# buf_full_bts_v21.net
KiCad netlist of a schematic drawn in EAGLE
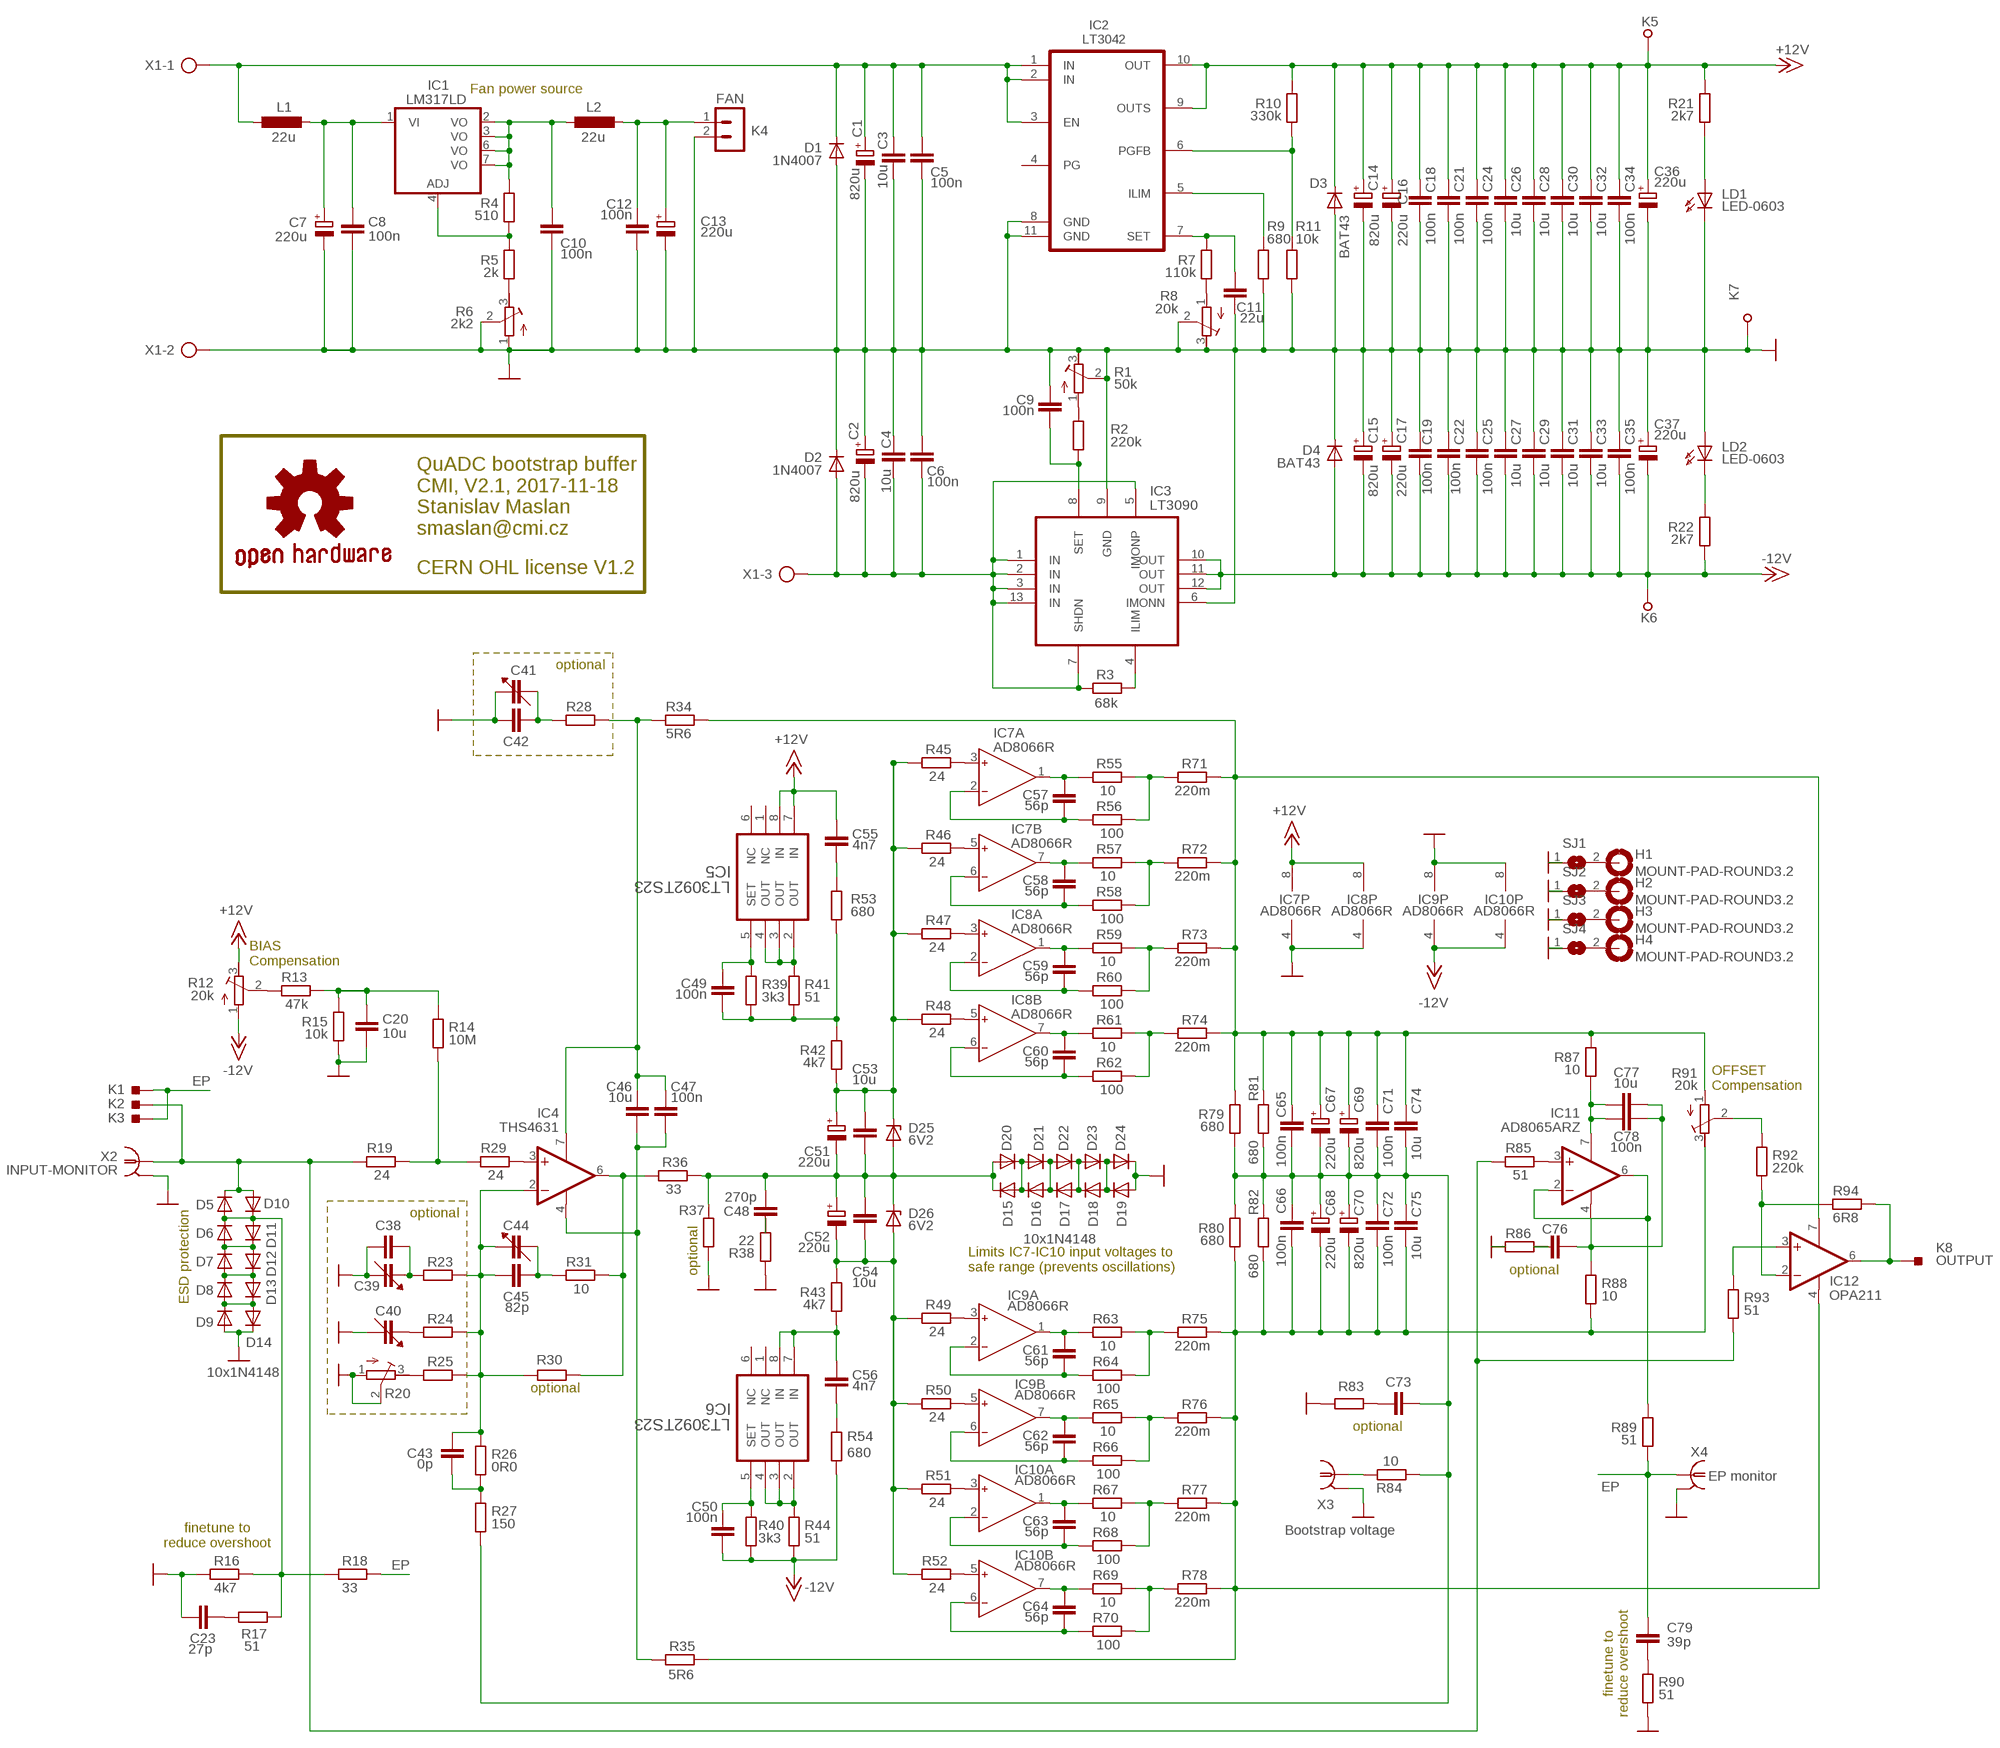
[diagram p0: schematic, sheet 1]

(export (version "E")
  (design (tool "Eeschema 10.0.6"))
  (components
    (comp (ref "C1")
      (value "820u")
      (footprint "eagle-import:E5-10,5")
      (libsource (lib "eagle-import") (part "CPOL-EUE5-10.5"))
    )
    (comp (ref "C2")
      (value "820u")
      (footprint "eagle-import:E5-10,5")
      (libsource (lib "eagle-import") (part "CPOL-EUE5-10.5"))
    )
    (comp (ref "C3")
      (value "10u")
      (footprint "eagle-import:C1210K")
      (libsource (lib "eagle-import") (part "C-EUC1210K"))
    )
    (comp (ref "C4")
      (value "10u")
      (footprint "eagle-import:C1210K")
      (libsource (lib "eagle-import") (part "C-EUC1210K"))
    )
    (comp (ref "C5")
      (value "100n")
      (footprint "eagle-import:X0805")
      (libsource (lib "eagle-import") (part "C-EUX0805"))
    )
    (comp (ref "C6")
      (value "100n")
      (footprint "eagle-import:X0805")
      (libsource (lib "eagle-import") (part "C-EUX0805"))
    )
    (comp (ref "C7")
      (value "220u")
      (footprint "eagle-import:E2,5-7")
      (libsource (lib "eagle-import") (part "CPOL-EUE2.5-7"))
    )
    (comp (ref "C8")
      (value "100n")
      (footprint "eagle-import:X0805")
      (libsource (lib "eagle-import") (part "C-EUX0805"))
    )
    (comp (ref "C9")
      (value "100n")
      (footprint "eagle-import:X0805")
      (libsource (lib "eagle-import") (part "C-EUX0805"))
    )
    (comp (ref "C10")
      (value "100n")
      (footprint "eagle-import:X0805")
      (libsource (lib "eagle-import") (part "C-EUX0805"))
    )
    (comp (ref "C11")
      (value "22u")
      (footprint "eagle-import:C1210K")
      (libsource (lib "eagle-import") (part "C-EUC1210K"))
    )
    (comp (ref "C12")
      (value "100n")
      (footprint "eagle-import:X0805")
      (libsource (lib "eagle-import") (part "C-EUX0805"))
    )
    (comp (ref "C13")
      (value "220u")
      (footprint "eagle-import:E2,5-7")
      (libsource (lib "eagle-import") (part "CPOL-EUE2.5-7"))
    )
    (comp (ref "C14")
      (value "820u")
      (footprint "eagle-import:E5-10,5")
      (libsource (lib "eagle-import") (part "CPOL-EUE5-10.5"))
    )
    (comp (ref "C15")
      (value "820u")
      (footprint "eagle-import:E5-10,5")
      (libsource (lib "eagle-import") (part "CPOL-EUE5-10.5"))
    )
    (comp (ref "C16")
      (value "220u")
      (footprint "eagle-import:E2,5-7")
      (libsource (lib "eagle-import") (part "CPOL-EUE2.5-7"))
    )
    (comp (ref "C17")
      (value "220u")
      (footprint "eagle-import:E2,5-7")
      (libsource (lib "eagle-import") (part "CPOL-EUE2.5-7"))
    )
    (comp (ref "C18")
      (value "100n")
      (footprint "eagle-import:X0805")
      (libsource (lib "eagle-import") (part "C-EUX0805"))
    )
    (comp (ref "C19")
      (value "100n")
      (footprint "eagle-import:X0805")
      (libsource (lib "eagle-import") (part "C-EUX0805"))
    )
    (comp (ref "C20")
      (value "10u")
      (footprint "eagle-import:C1210K")
      (libsource (lib "eagle-import") (part "C-EUC1210K"))
    )
    (comp (ref "C21")
      (value "100n")
      (footprint "eagle-import:X0805")
      (libsource (lib "eagle-import") (part "C-EUX0805"))
    )
    (comp (ref "C22")
      (value "100n")
      (footprint "eagle-import:X0805")
      (libsource (lib "eagle-import") (part "C-EUX0805"))
    )
    (comp (ref "C23")
      (value "27p")
      (footprint "eagle-import:C025-024X044")
      (libsource (lib "eagle-import") (part "C-EU025-024X044"))
    )
    (comp (ref "C24")
      (value "100n")
      (footprint "eagle-import:X0805")
      (libsource (lib "eagle-import") (part "C-EUX0805"))
    )
    (comp (ref "C25")
      (value "100n")
      (footprint "eagle-import:X0805")
      (libsource (lib "eagle-import") (part "C-EUX0805"))
    )
    (comp (ref "C26")
      (value "10u")
      (footprint "eagle-import:C1210K")
      (libsource (lib "eagle-import") (part "C-EUC1210K"))
    )
    (comp (ref "C27")
      (value "10u")
      (footprint "eagle-import:C1210K")
      (libsource (lib "eagle-import") (part "C-EUC1210K"))
    )
    (comp (ref "C28")
      (value "10u")
      (footprint "eagle-import:C1210K")
      (libsource (lib "eagle-import") (part "C-EUC1210K"))
    )
    (comp (ref "C29")
      (value "10u")
      (footprint "eagle-import:C1210K")
      (libsource (lib "eagle-import") (part "C-EUC1210K"))
    )
    (comp (ref "C30")
      (value "10u")
      (footprint "eagle-import:C1210K")
      (libsource (lib "eagle-import") (part "C-EUC1210K"))
    )
    (comp (ref "C31")
      (value "10u")
      (footprint "eagle-import:C1210K")
      (libsource (lib "eagle-import") (part "C-EUC1210K"))
    )
    (comp (ref "C32")
      (value "10u")
      (footprint "eagle-import:C1210K")
      (libsource (lib "eagle-import") (part "C-EUC1210K"))
    )
    (comp (ref "C33")
      (value "10u")
      (footprint "eagle-import:C1210K")
      (libsource (lib "eagle-import") (part "C-EUC1210K"))
    )
    (comp (ref "C34")
      (value "100n")
      (footprint "eagle-import:X0805")
      (libsource (lib "eagle-import") (part "C-EUX0805"))
    )
    (comp (ref "C35")
      (value "100n")
      (footprint "eagle-import:X0805")
      (libsource (lib "eagle-import") (part "C-EUX0805"))
    )
    (comp (ref "C36")
      (value "220u")
      (footprint "eagle-import:E2,5-7")
      (libsource (lib "eagle-import") (part "CPOL-EUE2.5-7"))
    )
    (comp (ref "C37")
      (value "220u")
      (footprint "eagle-import:E2,5-7")
      (libsource (lib "eagle-import") (part "CPOL-EUE2.5-7"))
    )
    (comp (ref "C38")
      (value "C-EU025-024X044")
      (footprint "eagle-import:C025-024X044")
      (libsource (lib "eagle-import") (part "C-EU025-024X044"))
    )
    (comp (ref "C39")
      (value "C_TRIMMER-9344")
      (footprint "eagle-import:CTRIMMER9344")
      (libsource (lib "eagle-import") (part "C_TRIMMER-9344"))
    )
    (comp (ref "C40")
      (value "C_TRIMMER-9344")
      (footprint "eagle-import:CTRIMMER9344")
      (libsource (lib "eagle-import") (part "C_TRIMMER-9344"))
    )
    (comp (ref "C41")
      (value "C_TRIMMER-9344")
      (footprint "eagle-import:CTRIMMER9344")
      (libsource (lib "eagle-import") (part "C_TRIMMER-9344"))
    )
    (comp (ref "C42")
      (value "C-EU025-024X044")
      (footprint "eagle-import:C025-024X044")
      (libsource (lib "eagle-import") (part "C-EU025-024X044"))
    )
    (comp (ref "C43")
      (value "0p")
      (footprint "eagle-import:C025-024X044")
      (libsource (lib "eagle-import") (part "C-EU025-024X044"))
    )
    (comp (ref "C44")
      (value "C_TRIMMER-9344")
      (footprint "eagle-import:CTRIMMER9344")
      (libsource (lib "eagle-import") (part "C_TRIMMER-9344"))
    )
    (comp (ref "C45")
      (value "82p")
      (footprint "eagle-import:C025-024X044")
      (libsource (lib "eagle-import") (part "C-EU025-024X044"))
    )
    (comp (ref "C46")
      (value "10u")
      (footprint "eagle-import:C1210K")
      (libsource (lib "eagle-import") (part "C-EUC1210K"))
    )
    (comp (ref "C47")
      (value "100n")
      (footprint "eagle-import:X0805")
      (libsource (lib "eagle-import") (part "C-EUX0805"))
    )
    (comp (ref "C48")
      (value "270p")
      (footprint "eagle-import:X0805")
      (libsource (lib "eagle-import") (part "C-EUX0805"))
    )
    (comp (ref "C49")
      (value "100n")
      (footprint "eagle-import:X0805")
      (libsource (lib "eagle-import") (part "C-EUX0805"))
    )
    (comp (ref "C50")
      (value "100n")
      (footprint "eagle-import:X0805")
      (libsource (lib "eagle-import") (part "C-EUX0805"))
    )
    (comp (ref "C51")
      (value "220u")
      (footprint "eagle-import:E2,5-7")
      (libsource (lib "eagle-import") (part "CPOL-EUE2.5-7"))
    )
    (comp (ref "C52")
      (value "220u")
      (footprint "eagle-import:E2,5-7")
      (libsource (lib "eagle-import") (part "CPOL-EUE2.5-7"))
    )
    (comp (ref "C53")
      (value "10u")
      (footprint "eagle-import:C1210K")
      (libsource (lib "eagle-import") (part "C-EUC1210K"))
    )
    (comp (ref "C54")
      (value "10u")
      (footprint "eagle-import:C1210K")
      (libsource (lib "eagle-import") (part "C-EUC1210K"))
    )
    (comp (ref "C55")
      (value "4n7")
      (footprint "eagle-import:C025-024X044")
      (libsource (lib "eagle-import") (part "C-EU025-024X044"))
    )
    (comp (ref "C56")
      (value "4n7")
      (footprint "eagle-import:C025-024X044")
      (libsource (lib "eagle-import") (part "C-EU025-024X044"))
    )
    (comp (ref "C57")
      (value "56p")
      (footprint "eagle-import:C025-024X044")
      (libsource (lib "eagle-import") (part "C-EU025-024X044"))
    )
    (comp (ref "C58")
      (value "56p")
      (footprint "eagle-import:C025-024X044")
      (libsource (lib "eagle-import") (part "C-EU025-024X044"))
    )
    (comp (ref "C59")
      (value "56p")
      (footprint "eagle-import:C025-024X044")
      (libsource (lib "eagle-import") (part "C-EU025-024X044"))
    )
    (comp (ref "C60")
      (value "56p")
      (footprint "eagle-import:C025-024X044")
      (libsource (lib "eagle-import") (part "C-EU025-024X044"))
    )
    (comp (ref "C61")
      (value "56p")
      (footprint "eagle-import:C025-024X044")
      (libsource (lib "eagle-import") (part "C-EU025-024X044"))
    )
    (comp (ref "C62")
      (value "56p")
      (footprint "eagle-import:C025-024X044")
      (libsource (lib "eagle-import") (part "C-EU025-024X044"))
    )
    (comp (ref "C63")
      (value "56p")
      (footprint "eagle-import:C025-024X044")
      (libsource (lib "eagle-import") (part "C-EU025-024X044"))
    )
    (comp (ref "C64")
      (value "56p")
      (footprint "eagle-import:C025-024X044")
      (libsource (lib "eagle-import") (part "C-EU025-024X044"))
    )
    (comp (ref "C65")
      (value "100n")
      (footprint "eagle-import:X0805")
      (libsource (lib "eagle-import") (part "C-EUX0805"))
    )
    (comp (ref "C66")
      (value "100n")
      (footprint "eagle-import:X0805")
      (libsource (lib "eagle-import") (part "C-EUX0805"))
    )
    (comp (ref "C67")
      (value "220u")
      (footprint "eagle-import:E2,5-7")
      (libsource (lib "eagle-import") (part "CPOL-EUE2.5-7"))
    )
    (comp (ref "C68")
      (value "220u")
      (footprint "eagle-import:E2,5-7")
      (libsource (lib "eagle-import") (part "CPOL-EUE2.5-7"))
    )
    (comp (ref "C69")
      (value "820u")
      (footprint "eagle-import:E5-10,5")
      (libsource (lib "eagle-import") (part "CPOL-EUE5-10.5"))
    )
    (comp (ref "C70")
      (value "820u")
      (footprint "eagle-import:E5-10,5")
      (libsource (lib "eagle-import") (part "CPOL-EUE5-10.5"))
    )
    (comp (ref "C71")
      (value "100n")
      (footprint "eagle-import:X0805")
      (libsource (lib "eagle-import") (part "C-EUX0805"))
    )
    (comp (ref "C72")
      (value "100n")
      (footprint "eagle-import:X0805")
      (libsource (lib "eagle-import") (part "C-EUX0805"))
    )
    (comp (ref "C73")
      (value "C-EU025-024X044")
      (footprint "eagle-import:C025-024X044")
      (libsource (lib "eagle-import") (part "C-EU025-024X044"))
    )
    (comp (ref "C74")
      (value "10u")
      (footprint "eagle-import:C1210K")
      (libsource (lib "eagle-import") (part "C-EUC1210K"))
    )
    (comp (ref "C75")
      (value "10u")
      (footprint "eagle-import:C1210K")
      (libsource (lib "eagle-import") (part "C-EUC1210K"))
    )
    (comp (ref "C76")
      (value "C-EU025-024X044")
      (footprint "eagle-import:C025-024X044")
      (libsource (lib "eagle-import") (part "C-EU025-024X044"))
    )
    (comp (ref "C77")
      (value "10u")
      (footprint "eagle-import:C1210K")
      (libsource (lib "eagle-import") (part "C-EUC1210K"))
    )
    (comp (ref "C78")
      (value "100n")
      (footprint "eagle-import:X0805")
      (libsource (lib "eagle-import") (part "C-EUX0805"))
    )
    (comp (ref "C79")
      (value "39p")
      (footprint "eagle-import:C025-024X044")
      (libsource (lib "eagle-import") (part "C-EU025-024X044"))
    )
    (comp (ref "D1")
      (value "1N4007")
      (footprint "eagle-import:DO-214AC")
      (libsource (lib "eagle-import") (part "DIODE-DO-214AC"))
    )
    (comp (ref "D2")
      (value "1N4007")
      (footprint "eagle-import:DO-214AC")
      (libsource (lib "eagle-import") (part "DIODE-DO-214AC"))
    )
    (comp (ref "D3")
      (value "BAT43")
      (footprint "eagle-import:SOD80C")
      (libsource (lib "eagle-import") (part "BAS32"))
    )
    (comp (ref "D4")
      (value "BAT43")
      (footprint "eagle-import:SOD80C")
      (libsource (lib "eagle-import") (part "BAS32"))
    )
    (comp (ref "D5")
      (value "DIODE-MICROMELF-W")
      (footprint "eagle-import:MICROMELF-W")
      (libsource (lib "eagle-import") (part "DIODE-MICROMELF-W"))
    )
    (comp (ref "D6")
      (value "DIODE-MICROMELF-W")
      (footprint "eagle-import:MICROMELF-W")
      (libsource (lib "eagle-import") (part "DIODE-MICROMELF-W"))
    )
    (comp (ref "D7")
      (value "DIODE-MICROMELF-W")
      (footprint "eagle-import:MICROMELF-W")
      (libsource (lib "eagle-import") (part "DIODE-MICROMELF-W"))
    )
    (comp (ref "D8")
      (value "DIODE-MICROMELF-W")
      (footprint "eagle-import:MICROMELF-W")
      (libsource (lib "eagle-import") (part "DIODE-MICROMELF-W"))
    )
    (comp (ref "D9")
      (value "DIODE-MICROMELF-W")
      (footprint "eagle-import:MICROMELF-W")
      (libsource (lib "eagle-import") (part "DIODE-MICROMELF-W"))
    )
    (comp (ref "D10")
      (value "DIODE-MICROMELF-W")
      (footprint "eagle-import:MICROMELF-W")
      (libsource (lib "eagle-import") (part "DIODE-MICROMELF-W"))
    )
    (comp (ref "D11")
      (value "DIODE-MICROMELF-W")
      (footprint "eagle-import:MICROMELF-W")
      (libsource (lib "eagle-import") (part "DIODE-MICROMELF-W"))
    )
    (comp (ref "D12")
      (value "DIODE-MICROMELF-W")
      (footprint "eagle-import:MICROMELF-W")
      (libsource (lib "eagle-import") (part "DIODE-MICROMELF-W"))
    )
    (comp (ref "D13")
      (value "DIODE-MICROMELF-W")
      (footprint "eagle-import:MICROMELF-W")
      (libsource (lib "eagle-import") (part "DIODE-MICROMELF-W"))
    )
    (comp (ref "D14")
      (value "10x1N4148")
      (footprint "eagle-import:MICROMELF-W")
      (libsource (lib "eagle-import") (part "DIODE-MICROMELF-W"))
    )
    (comp (ref "D15")
      (value "10x1N4148")
      (footprint "eagle-import:MICROMELF-W")
      (libsource (lib "eagle-import") (part "DIODE-MICROMELF-W"))
    )
    (comp (ref "D16")
      (value "DIODE-MICROMELF-W")
      (footprint "eagle-import:MICROMELF-W")
      (libsource (lib "eagle-import") (part "DIODE-MICROMELF-W"))
    )
    (comp (ref "D17")
      (value "DIODE-MICROMELF-W")
      (footprint "eagle-import:MICROMELF-W")
      (libsource (lib "eagle-import") (part "DIODE-MICROMELF-W"))
    )
    (comp (ref "D18")
      (value "DIODE-MICROMELF-W")
      (footprint "eagle-import:MICROMELF-W")
      (libsource (lib "eagle-import") (part "DIODE-MICROMELF-W"))
    )
    (comp (ref "D19")
      (value "DIODE-MICROMELF-W")
      (footprint "eagle-import:MICROMELF-W")
      (libsource (lib "eagle-import") (part "DIODE-MICROMELF-W"))
    )
    (comp (ref "D20")
      (value "DIODE-MICROMELF-W")
      (footprint "eagle-import:MICROMELF-W")
      (libsource (lib "eagle-import") (part "DIODE-MICROMELF-W"))
    )
    (comp (ref "D21")
      (value "DIODE-MICROMELF-W")
      (footprint "eagle-import:MICROMELF-W")
      (libsource (lib "eagle-import") (part "DIODE-MICROMELF-W"))
    )
    (comp (ref "D22")
      (value "DIODE-MICROMELF-W")
      (footprint "eagle-import:MICROMELF-W")
      (libsource (lib "eagle-import") (part "DIODE-MICROMELF-W"))
    )
    (comp (ref "D23")
      (value "DIODE-MICROMELF-W")
      (footprint "eagle-import:MICROMELF-W")
      (libsource (lib "eagle-import") (part "DIODE-MICROMELF-W"))
    )
    (comp (ref "D24")
      (value "DIODE-MICROMELF-W")
      (footprint "eagle-import:MICROMELF-W")
      (libsource (lib "eagle-import") (part "DIODE-MICROMELF-W"))
    )
    (comp (ref "D25")
      (value "6V2")
      (footprint "eagle-import:SOD80C")
      (libsource (lib "eagle-import") (part "ZENER-DIODESOD80C"))
    )
    (comp (ref "D26")
      (value "6V2")
      (footprint "eagle-import:SOD80C")
      (libsource (lib "eagle-import") (part "ZENER-DIODESOD80C"))
    )
    (comp (ref "GOLD_ORB_SM1")
      (value "OSHWLOGO_GOLD_ORB_MED")
      (footprint "eagle-import:OSHW1")
      (libsource (lib "eagle-import") (part "OSHWLOGO_GOLD_ORB_MED"))
    )
    (comp (ref "H1")
      (value "MOUNT-PAD-ROUND3.2")
      (footprint "eagle-import:3,2-PAD")
      (libsource (lib "eagle-import") (part "MOUNT-PAD-ROUND3.2"))
    )
    (comp (ref "H2")
      (value "MOUNT-PAD-ROUND3.2")
      (footprint "eagle-import:3,2-PAD")
      (libsource (lib "eagle-import") (part "MOUNT-PAD-ROUND3.2"))
    )
    (comp (ref "H3")
      (value "MOUNT-PAD-ROUND3.2")
      (footprint "eagle-import:3,2-PAD")
      (libsource (lib "eagle-import") (part "MOUNT-PAD-ROUND3.2"))
    )
    (comp (ref "H4")
      (value "MOUNT-PAD-ROUND3.2")
      (footprint "eagle-import:3,2-PAD")
      (libsource (lib "eagle-import") (part "MOUNT-PAD-ROUND3.2"))
    )
    (comp (ref "IC1")
      (value "LM317LD")
      (footprint "eagle-import:SO08")
      (libsource (lib "eagle-import") (part "LM317LD"))
    )
    (comp (ref "IC2")
      (value "LT3042")
      (footprint "eagle-import:SOP50P490X110-11N")
      (libsource (lib "eagle-import") (part "LT3042"))
    )
    (comp (ref "IC3")
      (value "LT3090")
      (footprint "eagle-import:SOP65P490X110-13N")
      (libsource (lib "eagle-import") (part "LT3090"))
    )
    (comp (ref "IC4")
      (value "THS4631")
      (footprint "eagle-import:SO8")
      (libsource (lib "eagle-import") (part "AD8065ARZ"))
    )
    (comp (ref "IC5")
      (value "LT3092TS23")
      (footprint "eagle-import:SOT65P280X100-8N")
      (libsource (lib "eagle-import") (part "LT3092TS23"))
    )
    (comp (ref "IC6")
      (value "LT3092TS23")
      (footprint "eagle-import:SOT65P280X100-8N")
      (libsource (lib "eagle-import") (part "LT3092TS23"))
    )
    (comp (ref "IC7")
      (value "AD8066R")
      (footprint "eagle-import:SO8")
      (libsource (lib "eagle-import") (part "AD8066R"))
    )
    (comp (ref "IC8")
      (value "AD8066R")
      (footprint "eagle-import:SO8")
      (libsource (lib "eagle-import") (part "AD8066R"))
    )
    (comp (ref "IC9")
      (value "AD8066R")
      (footprint "eagle-import:SO8")
      (libsource (lib "eagle-import") (part "AD8066R"))
    )
    (comp (ref "IC10")
      (value "AD8066R")
      (footprint "eagle-import:SO8")
      (libsource (lib "eagle-import") (part "AD8066R"))
    )
    (comp (ref "IC11")
      (value "AD8065ARZ")
      (footprint "eagle-import:SO8")
      (libsource (lib "eagle-import") (part "AD8065ARZ"))
    )
    (comp (ref "IC12")
      (value "OPA211")
      (footprint "eagle-import:SO8")
      (libsource (lib "eagle-import") (part "AD8065ARZ"))
    )
    (comp (ref "K1")
      (value "SP_RI")
      (footprint "eagle-import:SMD_1X1_S9")
      (libsource (lib "eagle-import") (part "SP_RI"))
    )
    (comp (ref "K2")
      (value "SP_RH")
      (footprint "eagle-import:SMD_1X1_S8")
      (libsource (lib "eagle-import") (part "SP_RH"))
    )
    (comp (ref "K3")
      (value "SP_RI")
      (footprint "eagle-import:SMD_1X1_S9")
      (libsource (lib "eagle-import") (part "SP_RI"))
    )
    (comp (ref "K4")
      (value "FAN")
      (footprint "eagle-import:MA02-1W")
      (libsource (lib "eagle-import") (part "MA02-1W"))
    )
    (comp (ref "K5")
      (value "SPP")
      (footprint "eagle-import:SP_PRO")
      (libsource (lib "eagle-import") (part "SPP"))
    )
    (comp (ref "K6")
      (value "SPP")
      (footprint "eagle-import:SP_PRO")
      (libsource (lib "eagle-import") (part "SPP"))
    )
    (comp (ref "K7")
      (value "SPP")
      (footprint "eagle-import:SP_PRO")
      (libsource (lib "eagle-import") (part "SPP"))
    )
    (comp (ref "K8")
      (value "OUTPUT")
      (footprint "eagle-import:SMD_1X1_S8")
      (libsource (lib "eagle-import") (part "SP_RH"))
    )
    (comp (ref "L1")
      (value "22u")
      (footprint "eagle-import:L3225M")
      (libsource (lib "eagle-import") (part "L-EUL3225M"))
    )
    (comp (ref "L2")
      (value "22u")
      (footprint "eagle-import:L3225M")
      (libsource (lib "eagle-import") (part "L-EUL3225M"))
    )
    (comp (ref "LD1")
      (value "LED-0603")
      (footprint "eagle-import:D0603")
      (libsource (lib "eagle-import") (part "LED-0603"))
    )
    (comp (ref "LD2")
      (value "LED-0603")
      (footprint "eagle-import:D0603")
      (libsource (lib "eagle-import") (part "LED-0603"))
    )
    (comp (ref "R1")
      (value "50k")
      (footprint "eagle-import:RTRIM3214W")
      (libsource (lib "eagle-import") (part "R-TRIMM3214W"))
    )
    (comp (ref "R2")
      (value "220k")
      (footprint "eagle-import:X0805")
      (libsource (lib "eagle-import") (part "R-EU_X0805"))
    )
    (comp (ref "R3")
      (value "68k")
      (footprint "eagle-import:X0805")
      (libsource (lib "eagle-import") (part "R-EU_X0805"))
    )
    (comp (ref "R4")
      (value "510")
      (footprint "eagle-import:X0805")
      (libsource (lib "eagle-import") (part "R-EU_X0805"))
    )
    (comp (ref "R5")
      (value "2k")
      (footprint "eagle-import:X0805")
      (libsource (lib "eagle-import") (part "R-EU_X0805"))
    )
    (comp (ref "R6")
      (value "2k2")
      (footprint "eagle-import:RT3364W")
      (libsource (lib "eagle-import") (part "RTRIM3364W"))
    )
    (comp (ref "R7")
      (value "110k")
      (footprint "eagle-import:X0805")
      (libsource (lib "eagle-import") (part "R-EU_X0805"))
    )
    (comp (ref "R8")
      (value "20k")
      (footprint "eagle-import:RTRIM3214W")
      (libsource (lib "eagle-import") (part "R-TRIMM3214W"))
    )
    (comp (ref "R9")
      (value "680")
      (footprint "eagle-import:X0805")
      (libsource (lib "eagle-import") (part "R-EU_X0805"))
    )
    (comp (ref "R10")
      (value "330k")
      (footprint "eagle-import:X0805")
      (libsource (lib "eagle-import") (part "R-EU_X0805"))
    )
    (comp (ref "R11")
      (value "10k")
      (footprint "eagle-import:X0805")
      (libsource (lib "eagle-import") (part "R-EU_X0805"))
    )
    (comp (ref "R12")
      (value "20k")
      (footprint "eagle-import:RTRIM3214W")
      (libsource (lib "eagle-import") (part "R-TRIMM3214W"))
    )
    (comp (ref "R13")
      (value "47k")
      (footprint "eagle-import:X0805")
      (libsource (lib "eagle-import") (part "R-EU_X0805"))
    )
    (comp (ref "R14")
      (value "10M")
      (footprint "eagle-import:X0805")
      (libsource (lib "eagle-import") (part "R-EU_X0805"))
    )
    (comp (ref "R15")
      (value "10k")
      (footprint "eagle-import:X0805")
      (libsource (lib "eagle-import") (part "R-EU_X0805"))
    )
    (comp (ref "R16")
      (value "4k7")
      (footprint "eagle-import:X0805")
      (libsource (lib "eagle-import") (part "R-EU_X0805"))
    )
    (comp (ref "R17")
      (value "51")
      (footprint "eagle-import:0207_2V")
      (libsource (lib "eagle-import") (part "R-EU_0207/2V"))
    )
    (comp (ref "R18")
      (value "33")
      (footprint "eagle-import:X0805")
      (libsource (lib "eagle-import") (part "R-EU_X0805"))
    )
    (comp (ref "R19")
      (value "24")
      (footprint "eagle-import:X0805")
      (libsource (lib "eagle-import") (part "R-EU_X0805"))
    )
    (comp (ref "R20")
      (value "R-TRIMM3214W")
      (footprint "eagle-import:RTRIM3214W")
      (libsource (lib "eagle-import") (part "R-TRIMM3214W"))
    )
    (comp (ref "R21")
      (value "2k7")
      (footprint "eagle-import:X0805")
      (libsource (lib "eagle-import") (part "R-EU_X0805"))
    )
    (comp (ref "R22")
      (value "2k7")
      (footprint "eagle-import:X0805")
      (libsource (lib "eagle-import") (part "R-EU_X0805"))
    )
    (comp (ref "R23")
      (value "R-EU_0207/2V")
      (footprint "eagle-import:0207_2V")
      (libsource (lib "eagle-import") (part "R-EU_0207/2V"))
    )
    (comp (ref "R24")
      (value "R-EU_0207/2V")
      (footprint "eagle-import:0207_2V")
      (libsource (lib "eagle-import") (part "R-EU_0207/2V"))
    )
    (comp (ref "R25")
      (value "R-EU_0207/2V")
      (footprint "eagle-import:0207_2V")
      (libsource (lib "eagle-import") (part "R-EU_0207/2V"))
    )
    (comp (ref "R26")
      (value "0R0")
      (footprint "eagle-import:0207_2V")
      (libsource (lib "eagle-import") (part "R-EU_0207/2V"))
    )
    (comp (ref "R27")
      (value "150")
      (footprint "eagle-import:0207_2V")
      (libsource (lib "eagle-import") (part "R-EU_0207/2V"))
    )
    (comp (ref "R28")
      (value "R-EU_0207/2V")
      (footprint "eagle-import:0207_2V")
      (libsource (lib "eagle-import") (part "R-EU_0207/2V"))
    )
    (comp (ref "R29")
      (value "24")
      (footprint "eagle-import:X0805")
      (libsource (lib "eagle-import") (part "R-EU_X0805"))
    )
    (comp (ref "R30")
      (value "R-EU_0207/2V")
      (footprint "eagle-import:0207_2V")
      (libsource (lib "eagle-import") (part "R-EU_0207/2V"))
    )
    (comp (ref "R31")
      (value "10")
      (footprint "eagle-import:0207_2V")
      (libsource (lib "eagle-import") (part "R-EU_0207/2V"))
    )
    (comp (ref "R34")
      (value "5R6")
      (footprint "eagle-import:X0805")
      (libsource (lib "eagle-import") (part "R-EU_X0805"))
    )
    (comp (ref "R35")
      (value "5R6")
      (footprint "eagle-import:X0805")
      (libsource (lib "eagle-import") (part "R-EU_X0805"))
    )
    (comp (ref "R36")
      (value "33")
      (footprint "eagle-import:0207_2V")
      (libsource (lib "eagle-import") (part "R-EU_0207/2V"))
    )
    (comp (ref "R37")
      (value "R-EU_0207/2V")
      (footprint "eagle-import:0207_2V")
      (libsource (lib "eagle-import") (part "R-EU_0207/2V"))
    )
    (comp (ref "R38")
      (value "22")
      (footprint "eagle-import:X0805")
      (libsource (lib "eagle-import") (part "R-EU_X0805"))
    )
    (comp (ref "R39")
      (value "3k3")
      (footprint "eagle-import:X0805")
      (libsource (lib "eagle-import") (part "R-EU_X0805"))
    )
    (comp (ref "R40")
      (value "3k3")
      (footprint "eagle-import:X0805")
      (libsource (lib "eagle-import") (part "R-EU_X0805"))
    )
    (comp (ref "R41")
      (value "51")
      (footprint "eagle-import:X0805")
      (libsource (lib "eagle-import") (part "R-EU_X0805"))
    )
    (comp (ref "R42")
      (value "4k7")
      (footprint "eagle-import:X0805")
      (libsource (lib "eagle-import") (part "R-EU_X0805"))
    )
    (comp (ref "R43")
      (value "4k7")
      (footprint "eagle-import:X0805")
      (libsource (lib "eagle-import") (part "R-EU_X0805"))
    )
    (comp (ref "R44")
      (value "51")
      (footprint "eagle-import:X0805")
      (libsource (lib "eagle-import") (part "R-EU_X0805"))
    )
    (comp (ref "R45")
      (value "24")
      (footprint "eagle-import:X0805")
      (libsource (lib "eagle-import") (part "R-EU_X0805"))
    )
    (comp (ref "R46")
      (value "24")
      (footprint "eagle-import:X0805")
      (libsource (lib "eagle-import") (part "R-EU_X0805"))
    )
    (comp (ref "R47")
      (value "24")
      (footprint "eagle-import:X0805")
      (libsource (lib "eagle-import") (part "R-EU_X0805"))
    )
    (comp (ref "R48")
      (value "24")
      (footprint "eagle-import:X0805")
      (libsource (lib "eagle-import") (part "R-EU_X0805"))
    )
    (comp (ref "R49")
      (value "24")
      (footprint "eagle-import:X0805")
      (libsource (lib "eagle-import") (part "R-EU_X0805"))
    )
    (comp (ref "R50")
      (value "24")
      (footprint "eagle-import:X0805")
      (libsource (lib "eagle-import") (part "R-EU_X0805"))
    )
    (comp (ref "R51")
      (value "24")
      (footprint "eagle-import:X0805")
      (libsource (lib "eagle-import") (part "R-EU_X0805"))
    )
    (comp (ref "R52")
      (value "24")
      (footprint "eagle-import:X0805")
      (libsource (lib "eagle-import") (part "R-EU_X0805"))
    )
    (comp (ref "R53")
      (value "680")
      (footprint "eagle-import:0207_2V")
      (libsource (lib "eagle-import") (part "R-EU_0207/2V"))
    )
    (comp (ref "R54")
      (value "680")
      (footprint "eagle-import:0207_2V")
      (libsource (lib "eagle-import") (part "R-EU_0207/2V"))
    )
    (comp (ref "R55")
      (value "10")
      (footprint "eagle-import:0207_2V")
      (libsource (lib "eagle-import") (part "R-EU_0207/2V"))
    )
    (comp (ref "R56")
      (value "100")
      (footprint "eagle-import:0207_2V")
      (libsource (lib "eagle-import") (part "R-EU_0207/2V"))
    )
    (comp (ref "R57")
      (value "10")
      (footprint "eagle-import:0207_2V")
      (libsource (lib "eagle-import") (part "R-EU_0207/2V"))
    )
    (comp (ref "R58")
      (value "100")
      (footprint "eagle-import:0207_2V")
      (libsource (lib "eagle-import") (part "R-EU_0207/2V"))
    )
    (comp (ref "R59")
      (value "10")
      (footprint "eagle-import:0207_2V")
      (libsource (lib "eagle-import") (part "R-EU_0207/2V"))
    )
    (comp (ref "R60")
      (value "100")
      (footprint "eagle-import:0207_2V")
      (libsource (lib "eagle-import") (part "R-EU_0207/2V"))
    )
    (comp (ref "R61")
      (value "10")
      (footprint "eagle-import:0207_2V")
      (libsource (lib "eagle-import") (part "R-EU_0207/2V"))
    )
    (comp (ref "R62")
      (value "100")
      (footprint "eagle-import:0207_2V")
      (libsource (lib "eagle-import") (part "R-EU_0207/2V"))
    )
    (comp (ref "R63")
      (value "10")
      (footprint "eagle-import:0207_2V")
      (libsource (lib "eagle-import") (part "R-EU_0207/2V"))
    )
    (comp (ref "R64")
      (value "100")
      (footprint "eagle-import:0207_2V")
      (libsource (lib "eagle-import") (part "R-EU_0207/2V"))
    )
    (comp (ref "R65")
      (value "10")
      (footprint "eagle-import:0207_2V")
      (libsource (lib "eagle-import") (part "R-EU_0207/2V"))
    )
    (comp (ref "R66")
      (value "100")
      (footprint "eagle-import:0207_2V")
      (libsource (lib "eagle-import") (part "R-EU_0207/2V"))
    )
    (comp (ref "R67")
      (value "10")
      (footprint "eagle-import:0207_2V")
      (libsource (lib "eagle-import") (part "R-EU_0207/2V"))
    )
    (comp (ref "R68")
      (value "100")
      (footprint "eagle-import:0207_2V")
      (libsource (lib "eagle-import") (part "R-EU_0207/2V"))
    )
    (comp (ref "R69")
      (value "10")
      (footprint "eagle-import:0207_2V")
      (libsource (lib "eagle-import") (part "R-EU_0207/2V"))
    )
    (comp (ref "R70")
      (value "100")
      (footprint "eagle-import:0207_2V")
      (libsource (lib "eagle-import") (part "R-EU_0207/2V"))
    )
    (comp (ref "R71")
      (value "220m")
      (footprint "eagle-import:R1210")
      (libsource (lib "eagle-import") (part "R-EU_R1210"))
    )
    (comp (ref "R72")
      (value "220m")
      (footprint "eagle-import:R1210")
      (libsource (lib "eagle-import") (part "R-EU_R1210"))
    )
    (comp (ref "R73")
      (value "220m")
      (footprint "eagle-import:R1210")
      (libsource (lib "eagle-import") (part "R-EU_R1210"))
    )
    (comp (ref "R74")
      (value "220m")
      (footprint "eagle-import:R1210")
      (libsource (lib "eagle-import") (part "R-EU_R1210"))
    )
    (comp (ref "R75")
      (value "220m")
      (footprint "eagle-import:R1210")
      (libsource (lib "eagle-import") (part "R-EU_R1210"))
    )
    (comp (ref "R76")
      (value "220m")
      (footprint "eagle-import:R1210")
      (libsource (lib "eagle-import") (part "R-EU_R1210"))
    )
    (comp (ref "R77")
      (value "220m")
      (footprint "eagle-import:R1210")
      (libsource (lib "eagle-import") (part "R-EU_R1210"))
    )
    (comp (ref "R78")
      (value "220m")
      (footprint "eagle-import:R1210")
      (libsource (lib "eagle-import") (part "R-EU_R1210"))
    )
    (comp (ref "R79")
      (value "680")
      (footprint "eagle-import:X0805")
      (libsource (lib "eagle-import") (part "R-EU_X0805"))
    )
    (comp (ref "R80")
      (value "680")
      (footprint "eagle-import:X0805")
      (libsource (lib "eagle-import") (part "R-EU_X0805"))
    )
    (comp (ref "R81")
      (value "680")
      (footprint "eagle-import:X0805")
      (libsource (lib "eagle-import") (part "R-EU_X0805"))
    )
    (comp (ref "R82")
      (value "680")
      (footprint "eagle-import:X0805")
      (libsource (lib "eagle-import") (part "R-EU_X0805"))
    )
    (comp (ref "R83")
      (value "R-EU_0207/2V")
      (footprint "eagle-import:0207_2V")
      (libsource (lib "eagle-import") (part "R-EU_0207/2V"))
    )
    (comp (ref "R84")
      (value "10")
      (footprint "eagle-import:0207_2V")
      (libsource (lib "eagle-import") (part "R-EU_0207/2V"))
    )
    (comp (ref "R85")
      (value "51")
      (footprint "eagle-import:X0805")
      (libsource (lib "eagle-import") (part "R-EU_X0805"))
    )
    (comp (ref "R86")
      (value "R-EU_0207/2V")
      (footprint "eagle-import:0207_2V")
      (libsource (lib "eagle-import") (part "R-EU_0207/2V"))
    )
    (comp (ref "R87")
      (value "10")
      (footprint "eagle-import:X0805")
      (libsource (lib "eagle-import") (part "R-EU_X0805"))
    )
    (comp (ref "R88")
      (value "10")
      (footprint "eagle-import:X0805")
      (libsource (lib "eagle-import") (part "R-EU_X0805"))
    )
    (comp (ref "R89")
      (value "51")
      (footprint "eagle-import:X0805")
      (libsource (lib "eagle-import") (part "R-EU_X0805"))
    )
    (comp (ref "R90")
      (value "51")
      (footprint "eagle-import:0207_2V")
      (libsource (lib "eagle-import") (part "R-EU_0207/2V"))
    )
    (comp (ref "R91")
      (value "20k")
      (footprint "eagle-import:RTRIM3214W")
      (libsource (lib "eagle-import") (part "R-TRIMM3214W"))
    )
    (comp (ref "R92")
      (value "220k")
      (footprint "eagle-import:X0805")
      (libsource (lib "eagle-import") (part "R-EU_X0805"))
    )
    (comp (ref "R93")
      (value "51")
      (footprint "eagle-import:X0805")
      (libsource (lib "eagle-import") (part "R-EU_X0805"))
    )
    (comp (ref "R94")
      (value "6R8")
      (footprint "eagle-import:X0805")
      (libsource (lib "eagle-import") (part "R-EU_X0805"))
    )
    (comp (ref "SJ1") (value "SJ") (footprint "eagle-import:SJ") (libsource (lib "eagle-import") (part "SJ")))
    (comp (ref "SJ2") (value "SJ") (footprint "eagle-import:SJ") (libsource (lib "eagle-import") (part "SJ")))
    (comp (ref "SJ3") (value "SJ") (footprint "eagle-import:SJ") (libsource (lib "eagle-import") (part "SJ")))
    (comp (ref "SJ4") (value "SJ") (footprint "eagle-import:SJ") (libsource (lib "eagle-import") (part "SJ")))
    (comp (ref "X1")
      (value "AK500/3")
      (footprint "eagle-import:AK500_3")
      (libsource (lib "eagle-import") (part "AK500/3"))
    )
    (comp (ref "X2")
      (value "INPUT-MONITOR")
      (footprint "eagle-import:A1944")
      (libsource (lib "eagle-import") (part "A1944-50"))
    )
    (comp (ref "X3")
      (value "Bootstrap voltage")
      (footprint "eagle-import:A1944")
      (libsource (lib "eagle-import") (part "A1944-50"))
    )
    (comp (ref "X4")
      (value "EP monitor")
      (footprint "eagle-import:A1944")
      (libsource (lib "eagle-import") (part "A1944-50"))
    )
  )
  (nets
    (net (code "1") (name "+12V") (class "Default")
      (node (ref "C14") (pin "+") (pinfunction "+_+") (pintype "passive"))
      (node (ref "C16") (pin "+") (pinfunction "+_+") (pintype "passive"))
      (node (ref "C18") (pin "P$1") (pinfunction "1_P$1") (pintype "passive"))
      (node (ref "C21") (pin "P$1") (pinfunction "1_P$1") (pintype "passive"))
      (node (ref "C24") (pin "P$1") (pinfunction "1_P$1") (pintype "passive"))
      (node (ref "C26") (pin "1") (pinfunction "1_1") (pintype "passive"))
      (node (ref "C28") (pin "1") (pinfunction "1_1") (pintype "passive"))
      (node (ref "C30") (pin "1") (pinfunction "1_1") (pintype "passive"))
      (node (ref "C32") (pin "1") (pinfunction "1_1") (pintype "passive"))
      (node (ref "C34") (pin "P$1") (pinfunction "1_P$1") (pintype "passive"))
      (node (ref "C36") (pin "+") (pinfunction "+_+") (pintype "passive"))
      (node (ref "C55") (pin "1") (pinfunction "1_1") (pintype "passive"))
      (node (ref "D3") (pin "C") (pinfunction "C_C") (pintype "passive"))
      (node (ref "IC2") (pin "10") (pinfunction "OUT_10") (pintype "output"))
      (node (ref "IC2") (pin "9") (pinfunction "OUTS_9") (pintype "input"))
      (node (ref "IC5") (pin "7") (pinfunction "IN_7") (pintype "power_in"))
      (node (ref "IC5") (pin "8") (pinfunction "IN_8") (pintype "power_in"))
      (node (ref "IC7") (pin "8") (pinfunction "V+_8") (pintype "power_in"))
      (node (ref "IC8") (pin "8") (pinfunction "V+_8") (pintype "power_in"))
      (node (ref "K5") (pin "P$1") (pinfunction "P$1_P$1") (pintype "passive"))
      (node (ref "R10") (pin "P$2") (pinfunction "2_P$2") (pintype "passive"))
      (node (ref "R12") (pin "3") (pinfunction "E_3") (pintype "passive"))
      (node (ref "R21") (pin "P$2") (pinfunction "2_P$2") (pintype "passive"))
    )
    (net (code "2") (name "-12V") (class "Default")
      (node (ref "C15") (pin "-") (pinfunction "-_-") (pintype "passive"))
      (node (ref "C17") (pin "-") (pinfunction "-_-") (pintype "passive"))
      (node (ref "C19") (pin "P$2") (pinfunction "2_P$2") (pintype "passive"))
      (node (ref "C22") (pin "P$2") (pinfunction "2_P$2") (pintype "passive"))
      (node (ref "C25") (pin "P$2") (pinfunction "2_P$2") (pintype "passive"))
      (node (ref "C27") (pin "2") (pinfunction "2_2") (pintype "passive"))
      (node (ref "C29") (pin "2") (pinfunction "2_2") (pintype "passive"))
      (node (ref "C31") (pin "2") (pinfunction "2_2") (pintype "passive"))
      (node (ref "C33") (pin "2") (pinfunction "2_2") (pintype "passive"))
      (node (ref "C35") (pin "P$2") (pinfunction "2_P$2") (pintype "passive"))
      (node (ref "C37") (pin "-") (pinfunction "-_-") (pintype "passive"))
      (node (ref "C50") (pin "P$2") (pinfunction "2_P$2") (pintype "passive"))
      (node (ref "D4") (pin "A") (pinfunction "A_A") (pintype "passive"))
      (node (ref "IC10") (pin "4") (pinfunction "V-_4") (pintype "power_in"))
      (node (ref "IC3") (pin "10") (pinfunction "OUT_10") (pintype "output"))
      (node (ref "IC3") (pin "11") (pinfunction "OUT_11") (pintype "output"))
      (node (ref "IC3") (pin "12") (pinfunction "OUT_12") (pintype "output"))
      (node (ref "IC9") (pin "4") (pinfunction "V-_4") (pintype "power_in"))
      (node (ref "K6") (pin "P$1") (pinfunction "P$1_P$1") (pintype "passive"))
      (node (ref "R12") (pin "1") (pinfunction "A_1") (pintype "passive"))
      (node (ref "R22") (pin "P$1") (pinfunction "1_P$1") (pintype "passive"))
      (node (ref "R40") (pin "P$1") (pinfunction "1_P$1") (pintype "passive"))
      (node (ref "R44") (pin "P$1") (pinfunction "1_P$1") (pintype "passive"))
      (node (ref "R54") (pin "1") (pinfunction "1_1") (pintype "passive"))
    )
    (net (code "3") (name "/EP") (class "Default")
      (node (ref "C79") (pin "2") (pinfunction "2_2") (pintype "passive"))
      (node (ref "K1") (pin "1") (pinfunction "1_1") (pintype "passive"))
      (node (ref "K3") (pin "1") (pinfunction "1_1") (pintype "passive"))
      (node (ref "R18") (pin "P$1") (pinfunction "1_P$1") (pintype "passive"))
      (node (ref "R89") (pin "P$1") (pinfunction "1_P$1") (pintype "passive"))
      (node (ref "X4") (pin "1") (pinfunction "1_1") (pintype "passive"))
    )
    (net (code "4") (name "GND") (class "Default")
      (node (ref "C1") (pin "-") (pinfunction "-_-") (pintype "passive"))
      (node (ref "C10") (pin "P$2") (pinfunction "2_P$2") (pintype "passive"))
      (node (ref "C11") (pin "2") (pinfunction "2_2") (pintype "passive"))
      (node (ref "C12") (pin "P$2") (pinfunction "2_P$2") (pintype "passive"))
      (node (ref "C13") (pin "-") (pinfunction "-_-") (pintype "passive"))
      (node (ref "C14") (pin "-") (pinfunction "-_-") (pintype "passive"))
      (node (ref "C15") (pin "+") (pinfunction "+_+") (pintype "passive"))
      (node (ref "C16") (pin "-") (pinfunction "-_-") (pintype "passive"))
      (node (ref "C17") (pin "+") (pinfunction "+_+") (pintype "passive"))
      (node (ref "C18") (pin "P$2") (pinfunction "2_P$2") (pintype "passive"))
      (node (ref "C19") (pin "P$1") (pinfunction "1_P$1") (pintype "passive"))
      (node (ref "C2") (pin "+") (pinfunction "+_+") (pintype "passive"))
      (node (ref "C20") (pin "2") (pinfunction "2_2") (pintype "passive"))
      (node (ref "C21") (pin "P$2") (pinfunction "2_P$2") (pintype "passive"))
      (node (ref "C22") (pin "P$1") (pinfunction "1_P$1") (pintype "passive"))
      (node (ref "C23") (pin "1") (pinfunction "1_1") (pintype "passive"))
      (node (ref "C24") (pin "P$2") (pinfunction "2_P$2") (pintype "passive"))
      (node (ref "C25") (pin "P$1") (pinfunction "1_P$1") (pintype "passive"))
      (node (ref "C26") (pin "2") (pinfunction "2_2") (pintype "passive"))
      (node (ref "C27") (pin "1") (pinfunction "1_1") (pintype "passive"))
      (node (ref "C28") (pin "2") (pinfunction "2_2") (pintype "passive"))
      (node (ref "C29") (pin "1") (pinfunction "1_1") (pintype "passive"))
      (node (ref "C3") (pin "2") (pinfunction "2_2") (pintype "passive"))
      (node (ref "C30") (pin "2") (pinfunction "2_2") (pintype "passive"))
      (node (ref "C31") (pin "1") (pinfunction "1_1") (pintype "passive"))
      (node (ref "C32") (pin "2") (pinfunction "2_2") (pintype "passive"))
      (node (ref "C33") (pin "1") (pinfunction "1_1") (pintype "passive"))
      (node (ref "C34") (pin "P$2") (pinfunction "2_P$2") (pintype "passive"))
      (node (ref "C35") (pin "P$1") (pinfunction "1_P$1") (pintype "passive"))
      (node (ref "C36") (pin "-") (pinfunction "-_-") (pintype "passive"))
      (node (ref "C37") (pin "+") (pinfunction "+_+") (pintype "passive"))
      (node (ref "C38") (pin "2") (pinfunction "2_2") (pintype "passive"))
      (node (ref "C39") (pin "2") (pinfunction "1_2") (pintype "passive"))
      (node (ref "C4") (pin "1") (pinfunction "1_1") (pintype "passive"))
      (node (ref "C40") (pin "2") (pinfunction "1_2") (pintype "passive"))
      (node (ref "C41") (pin "1") (pinfunction "2_1") (pintype "passive"))
      (node (ref "C42") (pin "1") (pinfunction "1_1") (pintype "passive"))
      (node (ref "C5") (pin "P$2") (pinfunction "2_P$2") (pintype "passive"))
      (node (ref "C6") (pin "P$1") (pinfunction "1_P$1") (pintype "passive"))
      (node (ref "C7") (pin "-") (pinfunction "-_-") (pintype "passive"))
      (node (ref "C8") (pin "P$2") (pinfunction "2_P$2") (pintype "passive"))
      (node (ref "C9") (pin "P$1") (pinfunction "1_P$1") (pintype "passive"))
      (node (ref "D1") (pin "A") (pinfunction "A_A") (pintype "passive"))
      (node (ref "D14") (pin "C") (pinfunction "C_C") (pintype "passive"))
      (node (ref "D19") (pin "A") (pinfunction "A_A") (pintype "passive"))
      (node (ref "D2") (pin "C") (pinfunction "C_C") (pintype "passive"))
      (node (ref "D24") (pin "C") (pinfunction "C_C") (pintype "passive"))
      (node (ref "D3") (pin "A") (pinfunction "A_A") (pintype "passive"))
      (node (ref "D4") (pin "C") (pinfunction "C_C") (pintype "passive"))
      (node (ref "D9") (pin "A") (pinfunction "A_A") (pintype "passive"))
      (node (ref "IC10") (pin "8") (pinfunction "V+_8") (pintype "power_in"))
      (node (ref "IC2") (pin "11") (pinfunction "GND_11") (pintype "power_in"))
      (node (ref "IC2") (pin "8") (pinfunction "GND_8") (pintype "power_in"))
      (node (ref "IC3") (pin "6") (pinfunction "IMONN_6") (pintype "passive"))
      (node (ref "IC3") (pin "9") (pinfunction "GND_9") (pintype "bidirectional"))
      (node (ref "IC7") (pin "4") (pinfunction "V-_4") (pintype "power_in"))
      (node (ref "IC8") (pin "4") (pinfunction "V-_4") (pintype "power_in"))
      (node (ref "IC9") (pin "8") (pinfunction "V+_8") (pintype "power_in"))
      (node (ref "K4") (pin "2") (pinfunction "2_2") (pintype "passive"))
      (node (ref "K7") (pin "P$1") (pinfunction "P$1_P$1") (pintype "passive"))
      (node (ref "LD1") (pin "K") (pinfunction "C_K") (pintype "passive"))
      (node (ref "LD2") (pin "A") (pinfunction "A_A") (pintype "passive"))
      (node (ref "R1") (pin "2") (pinfunction "S_2") (pintype "passive"))
      (node (ref "R1") (pin "3") (pinfunction "E_3") (pintype "passive"))
      (node (ref "R11") (pin "P$1") (pinfunction "1_P$1") (pintype "passive"))
      (node (ref "R15") (pin "P$1") (pinfunction "1_P$1") (pintype "passive"))
      (node (ref "R16") (pin "P$2") (pinfunction "2_P$2") (pintype "passive"))
      (node (ref "R20") (pin "1") (pinfunction "A_1") (pintype "passive"))
      (node (ref "R20") (pin "2") (pinfunction "S_2") (pintype "passive"))
      (node (ref "R37") (pin "1") (pinfunction "1_1") (pintype "passive"))
      (node (ref "R38") (pin "P$1") (pinfunction "1_P$1") (pintype "passive"))
      (node (ref "R6") (pin "1") (pinfunction "A_1") (pintype "passive"))
      (node (ref "R6") (pin "2") (pinfunction "S_2") (pintype "passive"))
      (node (ref "R8") (pin "2") (pinfunction "S_2") (pintype "passive"))
      (node (ref "R8") (pin "3") (pinfunction "E_3") (pintype "passive"))
      (node (ref "R83") (pin "1") (pinfunction "1_1") (pintype "passive"))
      (node (ref "R86") (pin "1") (pinfunction "1_1") (pintype "passive"))
      (node (ref "R9") (pin "P$1") (pinfunction "1_P$1") (pintype "passive"))
      (node (ref "R90") (pin "1") (pinfunction "1_1") (pintype "passive"))
      (node (ref "SJ1") (pin "1") (pinfunction "1_1") (pintype "passive"))
      (node (ref "SJ2") (pin "1") (pinfunction "1_1") (pintype "passive"))
      (node (ref "SJ3") (pin "1") (pinfunction "1_1") (pintype "passive"))
      (node (ref "SJ4") (pin "1") (pinfunction "1_1") (pintype "passive"))
      (node (ref "X1") (pin "2") (pinfunction "KL_2") (pintype "passive"))
      (node (ref "X2") (pin "2") (pinfunction "2_2") (pintype "passive"))
      (node (ref "X2") (pin "3") (pinfunction "2_3") (pintype "passive"))
      (node (ref "X2") (pin "4") (pinfunction "2_4") (pintype "passive"))
      (node (ref "X2") (pin "5") (pinfunction "2_5") (pintype "passive"))
      (node (ref "X3") (pin "2") (pinfunction "2_2") (pintype "passive"))
      (node (ref "X3") (pin "3") (pinfunction "2_3") (pintype "passive"))
      (node (ref "X3") (pin "4") (pinfunction "2_4") (pintype "passive"))
      (node (ref "X3") (pin "5") (pinfunction "2_5") (pintype "passive"))
      (node (ref "X4") (pin "2") (pinfunction "2_2") (pintype "passive"))
      (node (ref "X4") (pin "3") (pinfunction "2_3") (pintype "passive"))
      (node (ref "X4") (pin "4") (pinfunction "2_4") (pintype "passive"))
      (node (ref "X4") (pin "5") (pinfunction "2_5") (pintype "passive"))
    )
    (net (code "5") (name "Net-(C5-1)") (class "Default")
      (node (ref "C1") (pin "+") (pinfunction "+_+") (pintype "passive"))
      (node (ref "C3") (pin "1") (pinfunction "1_1") (pintype "passive"))
      (node (ref "C5") (pin "P$1") (pinfunction "1_P$1") (pintype "passive"))
      (node (ref "D1") (pin "C") (pinfunction "C_C") (pintype "passive"))
      (node (ref "IC2") (pin "1") (pinfunction "IN_1") (pintype "power_in"))
      (node (ref "IC2") (pin "2") (pinfunction "IN_2") (pintype "power_in"))
      (node (ref "IC2") (pin "3") (pinfunction "EN_3") (pintype "input"))
      (node (ref "L1") (pin "1") (pinfunction "1_1") (pintype "passive"))
      (node (ref "X1") (pin "1") (pinfunction "KL_1") (pintype "passive"))
    )
    (net (code "6") (name "Net-(C6-2)") (class "Default")
      (node (ref "C2") (pin "-") (pinfunction "-_-") (pintype "passive"))
      (node (ref "C4") (pin "2") (pinfunction "2_2") (pintype "passive"))
      (node (ref "C6") (pin "P$2") (pinfunction "2_P$2") (pintype "passive"))
      (node (ref "D2") (pin "A") (pinfunction "A_A") (pintype "passive"))
      (node (ref "IC3") (pin "1") (pinfunction "IN_1") (pintype "input"))
      (node (ref "IC3") (pin "13") (pinfunction "IN_13") (pintype "input"))
      (node (ref "IC3") (pin "2") (pinfunction "IN_2") (pintype "input"))
      (node (ref "IC3") (pin "3") (pinfunction "IN_3") (pintype "input"))
      (node (ref "IC3") (pin "5") (pinfunction "IMONP_5") (pintype "passive"))
      (node (ref "IC3") (pin "7") (pinfunction "SHDN_7") (pintype "input"))
      (node (ref "R3") (pin "P$2") (pinfunction "2_P$2") (pintype "passive"))
      (node (ref "X1") (pin "3") (pinfunction "KL_3") (pintype "passive"))
    )
    (net (code "7") (name "Net-(C8-1)") (class "Default")
      (node (ref "C7") (pin "+") (pinfunction "+_+") (pintype "passive"))
      (node (ref "C8") (pin "P$1") (pinfunction "1_P$1") (pintype "passive"))
      (node (ref "IC1") (pin "1") (pinfunction "VI_1") (pintype "input"))
      (node (ref "L1") (pin "2") (pinfunction "2_2") (pintype "passive"))
    )
    (net (code "8") (name "Net-(C9-2)") (class "Default")
      (node (ref "C9") (pin "P$2") (pinfunction "2_P$2") (pintype "passive"))
      (node (ref "IC3") (pin "8") (pinfunction "SET_8") (pintype "passive"))
      (node (ref "R2") (pin "P$1") (pinfunction "1_P$1") (pintype "passive"))
    )
    (net (code "9") (name "Net-(C10-1)") (class "Default")
      (node (ref "C10") (pin "P$1") (pinfunction "1_P$1") (pintype "passive"))
      (node (ref "IC1") (pin "2") (pinfunction "VO_2") (pintype "passive"))
      (node (ref "IC1") (pin "3") (pinfunction "VO_3") (pintype "passive"))
      (node (ref "IC1") (pin "6") (pinfunction "VO_6") (pintype "passive"))
      (node (ref "IC1") (pin "7") (pinfunction "VO_7") (pintype "passive"))
      (node (ref "L2") (pin "1") (pinfunction "1_1") (pintype "passive"))
      (node (ref "R4") (pin "P$2") (pinfunction "2_P$2") (pintype "passive"))
    )
    (net (code "10") (name "Net-(C12-1)") (class "Default")
      (node (ref "C12") (pin "P$1") (pinfunction "1_P$1") (pintype "passive"))
      (node (ref "C13") (pin "+") (pinfunction "+_+") (pintype "passive"))
      (node (ref "K4") (pin "1") (pinfunction "1_1") (pintype "passive"))
      (node (ref "L2") (pin "2") (pinfunction "2_2") (pintype "passive"))
    )
    (net (code "11") (name "Net-(C23-Pad2)") (class "Default")
      (node (ref "C23") (pin "2") (pinfunction "2_2") (pintype "passive"))
      (node (ref "R17") (pin "2") (pinfunction "2_2") (pintype "passive"))
    )
    (net (code "12") (name "Net-(C39-2)") (class "Default")
      (node (ref "C38") (pin "1") (pinfunction "1_1") (pintype "passive"))
      (node (ref "C39") (pin "1") (pinfunction "2_1") (pintype "passive"))
      (node (ref "R23") (pin "2") (pinfunction "2_2") (pintype "passive"))
    )
    (net (code "13") (name "Net-(C40-2)") (class "Default")
      (node (ref "C40") (pin "1") (pinfunction "2_1") (pintype "passive"))
      (node (ref "R24") (pin "2") (pinfunction "2_2") (pintype "passive"))
    )
    (net (code "14") (name "Net-(C41-1)") (class "Default")
      (node (ref "C41") (pin "2") (pinfunction "1_2") (pintype "passive"))
      (node (ref "C42") (pin "2") (pinfunction "2_2") (pintype "passive"))
      (node (ref "R28") (pin "1") (pinfunction "1_1") (pintype "passive"))
    )
    (net (code "15") (name "Net-(C43-Pad2)") (class "Default")
      (node (ref "C43") (pin "2") (pinfunction "2_2") (pintype "passive"))
      (node (ref "R26") (pin "2") (pinfunction "2_2") (pintype "passive"))
      (node (ref "R27") (pin "1") (pinfunction "1_1") (pintype "passive"))
    )
    (net (code "16") (name "Net-(C44-1)") (class "Default")
      (node (ref "C44") (pin "2") (pinfunction "1_2") (pintype "passive"))
      (node (ref "C45") (pin "2") (pinfunction "2_2") (pintype "passive"))
      (node (ref "R31") (pin "1") (pinfunction "1_1") (pintype "passive"))
    )
    (net (code "17") (name "Net-(C44-2)") (class "Default")
      (node (ref "C43") (pin "1") (pinfunction "1_1") (pintype "passive"))
      (node (ref "C44") (pin "1") (pinfunction "2_1") (pintype "passive"))
      (node (ref "C45") (pin "1") (pinfunction "1_1") (pintype "passive"))
      (node (ref "IC4") (pin "2") (pinfunction "-IN_2") (pintype "input"))
      (node (ref "R23") (pin "1") (pinfunction "1_1") (pintype "passive"))
      (node (ref "R24") (pin "1") (pinfunction "1_1") (pintype "passive"))
      (node (ref "R25") (pin "1") (pinfunction "1_1") (pintype "passive"))
      (node (ref "R26") (pin "1") (pinfunction "1_1") (pintype "passive"))
      (node (ref "R30") (pin "2") (pinfunction "2_2") (pintype "passive"))
    )
    (net (code "18") (name "Net-(C47-1)") (class "Default")
      (node (ref "C46") (pin "1") (pinfunction "1_1") (pintype "passive"))
      (node (ref "C47") (pin "P$1") (pinfunction "1_P$1") (pintype "passive"))
      (node (ref "IC4") (pin "7") (pinfunction "V+_7") (pintype "power_in"))
      (node (ref "R28") (pin "2") (pinfunction "2_2") (pintype "passive"))
      (node (ref "R34") (pin "P$1") (pinfunction "1_P$1") (pintype "passive"))
    )
    (net (code "19") (name "Net-(C47-2)") (class "Default")
      (node (ref "C46") (pin "2") (pinfunction "2_2") (pintype "passive"))
      (node (ref "C47") (pin "P$2") (pinfunction "2_P$2") (pintype "passive"))
      (node (ref "IC4") (pin "4") (pinfunction "V-_4") (pintype "power_in"))
      (node (ref "R35") (pin "P$2") (pinfunction "2_P$2") (pintype "passive"))
    )
    (net (code "20") (name "Net-(C48-1)") (class "Default")
      (node (ref "C48") (pin "P$1") (pinfunction "1_P$1") (pintype "passive"))
      (node (ref "R38") (pin "P$2") (pinfunction "2_P$2") (pintype "passive"))
    )
    (net (code "21") (name "Net-(C48-2)") (class "Default")
      (node (ref "C48") (pin "P$2") (pinfunction "2_P$2") (pintype "passive"))
      (node (ref "C51") (pin "-") (pinfunction "-_-") (pintype "passive"))
      (node (ref "C52") (pin "+") (pinfunction "+_+") (pintype "passive"))
      (node (ref "C53") (pin "2") (pinfunction "2_2") (pintype "passive"))
      (node (ref "C54") (pin "1") (pinfunction "1_1") (pintype "passive"))
      (node (ref "D15") (pin "C") (pinfunction "C_C") (pintype "passive"))
      (node (ref "D20") (pin "A") (pinfunction "A_A") (pintype "passive"))
      (node (ref "D25") (pin "A") (pinfunction "A_A") (pintype "passive"))
      (node (ref "D26") (pin "C") (pinfunction "C_C") (pintype "passive"))
      (node (ref "R36") (pin "2") (pinfunction "2_2") (pintype "passive"))
      (node (ref "R37") (pin "2") (pinfunction "2_2") (pintype "passive"))
    )
    (net (code "22") (name "Net-(C49-1)") (class "Default")
      (node (ref "C49") (pin "P$1") (pinfunction "1_P$1") (pintype "passive"))
      (node (ref "IC5") (pin "5") (pinfunction "SET_5") (pintype "input"))
      (node (ref "R39") (pin "P$2") (pinfunction "2_P$2") (pintype "passive"))
    )
    (net (code "23") (name "Net-(C49-2)") (class "Default")
      (node (ref "C49") (pin "P$2") (pinfunction "2_P$2") (pintype "passive"))
      (node (ref "R39") (pin "P$1") (pinfunction "1_P$1") (pintype "passive"))
      (node (ref "R41") (pin "P$1") (pinfunction "1_P$1") (pintype "passive"))
      (node (ref "R42") (pin "P$2") (pinfunction "2_P$2") (pintype "passive"))
      (node (ref "R53") (pin "1") (pinfunction "1_1") (pintype "passive"))
    )
    (net (code "24") (name "Net-(C50-1)") (class "Default")
      (node (ref "C50") (pin "P$1") (pinfunction "1_P$1") (pintype "passive"))
      (node (ref "IC6") (pin "5") (pinfunction "SET_5") (pintype "input"))
      (node (ref "R40") (pin "P$2") (pinfunction "2_P$2") (pintype "passive"))
    )
    (net (code "25") (name "Net-(C55-Pad2)") (class "Default")
      (node (ref "C55") (pin "2") (pinfunction "2_2") (pintype "passive"))
      (node (ref "R53") (pin "2") (pinfunction "2_2") (pintype "passive"))
    )
    (net (code "26") (name "Net-(C56-Pad2)") (class "Default")
      (node (ref "C56") (pin "2") (pinfunction "2_2") (pintype "passive"))
      (node (ref "R54") (pin "2") (pinfunction "2_2") (pintype "passive"))
    )
    (net (code "27") (name "Net-(C65-1)") (class "Default")
      (node (ref "C65") (pin "P$1") (pinfunction "1_P$1") (pintype "passive"))
      (node (ref "C67") (pin "+") (pinfunction "+_+") (pintype "passive"))
      (node (ref "C69") (pin "+") (pinfunction "+_+") (pintype "passive"))
      (node (ref "C71") (pin "P$1") (pinfunction "1_P$1") (pintype "passive"))
      (node (ref "C74") (pin "1") (pinfunction "1_1") (pintype "passive"))
      (node (ref "IC12") (pin "7") (pinfunction "V+_7") (pintype "power_in"))
      (node (ref "R34") (pin "P$2") (pinfunction "2_P$2") (pintype "passive"))
      (node (ref "R71") (pin "2") (pinfunction "2_2") (pintype "passive"))
      (node (ref "R72") (pin "2") (pinfunction "2_2") (pintype "passive"))
      (node (ref "R73") (pin "2") (pinfunction "2_2") (pintype "passive"))
      (node (ref "R74") (pin "2") (pinfunction "2_2") (pintype "passive"))
      (node (ref "R79") (pin "P$2") (pinfunction "2_P$2") (pintype "passive"))
      (node (ref "R81") (pin "P$2") (pinfunction "2_P$2") (pintype "passive"))
      (node (ref "R87") (pin "P$2") (pinfunction "2_P$2") (pintype "passive"))
      (node (ref "R91") (pin "1") (pinfunction "A_1") (pintype "passive"))
    )
    (net (code "28") (name "Net-(C65-2)") (class "Default")
      (node (ref "C65") (pin "P$2") (pinfunction "2_P$2") (pintype "passive"))
      (node (ref "C66") (pin "P$1") (pinfunction "1_P$1") (pintype "passive"))
      (node (ref "C67") (pin "-") (pinfunction "-_-") (pintype "passive"))
      (node (ref "C68") (pin "+") (pinfunction "+_+") (pintype "passive"))
      (node (ref "C69") (pin "-") (pinfunction "-_-") (pintype "passive"))
      (node (ref "C70") (pin "+") (pinfunction "+_+") (pintype "passive"))
      (node (ref "C71") (pin "P$2") (pinfunction "2_P$2") (pintype "passive"))
      (node (ref "C72") (pin "P$1") (pinfunction "1_P$1") (pintype "passive"))
      (node (ref "C73") (pin "2") (pinfunction "2_2") (pintype "passive"))
      (node (ref "C74") (pin "2") (pinfunction "2_2") (pintype "passive"))
      (node (ref "C75") (pin "1") (pinfunction "1_1") (pintype "passive"))
      (node (ref "R27") (pin "2") (pinfunction "2_2") (pintype "passive"))
      (node (ref "R79") (pin "P$1") (pinfunction "1_P$1") (pintype "passive"))
      (node (ref "R80") (pin "P$2") (pinfunction "2_P$2") (pintype "passive"))
      (node (ref "R81") (pin "P$1") (pinfunction "1_P$1") (pintype "passive"))
      (node (ref "R82") (pin "P$2") (pinfunction "2_P$2") (pintype "passive"))
      (node (ref "R84") (pin "1") (pinfunction "1_1") (pintype "passive"))
    )
    (net (code "29") (name "Net-(C66-2)") (class "Default")
      (node (ref "C66") (pin "P$2") (pinfunction "2_P$2") (pintype "passive"))
      (node (ref "C68") (pin "-") (pinfunction "-_-") (pintype "passive"))
      (node (ref "C70") (pin "-") (pinfunction "-_-") (pintype "passive"))
      (node (ref "C72") (pin "P$2") (pinfunction "2_P$2") (pintype "passive"))
      (node (ref "C75") (pin "2") (pinfunction "2_2") (pintype "passive"))
      (node (ref "IC12") (pin "4") (pinfunction "V-_4") (pintype "power_in"))
      (node (ref "R35") (pin "P$1") (pinfunction "1_P$1") (pintype "passive"))
      (node (ref "R75") (pin "2") (pinfunction "2_2") (pintype "passive"))
      (node (ref "R76") (pin "2") (pinfunction "2_2") (pintype "passive"))
      (node (ref "R77") (pin "2") (pinfunction "2_2") (pintype "passive"))
      (node (ref "R78") (pin "2") (pinfunction "2_2") (pintype "passive"))
      (node (ref "R80") (pin "P$1") (pinfunction "1_P$1") (pintype "passive"))
      (node (ref "R82") (pin "P$1") (pinfunction "1_P$1") (pintype "passive"))
      (node (ref "R88") (pin "P$1") (pinfunction "1_P$1") (pintype "passive"))
      (node (ref "R91") (pin "3") (pinfunction "E_3") (pintype "passive"))
    )
    (net (code "30") (name "Net-(C73-Pad1)") (class "Default")
      (node (ref "C73") (pin "1") (pinfunction "1_1") (pintype "passive"))
      (node (ref "R83") (pin "2") (pinfunction "2_2") (pintype "passive"))
    )
    (net (code "31") (name "Net-(C76-Pad1)") (class "Default")
      (node (ref "C76") (pin "1") (pinfunction "1_1") (pintype "passive"))
      (node (ref "R86") (pin "2") (pinfunction "2_2") (pintype "passive"))
    )
    (net (code "32") (name "Net-(C78-1)") (class "Default")
      (node (ref "C77") (pin "1") (pinfunction "1_1") (pintype "passive"))
      (node (ref "C78") (pin "P$1") (pinfunction "1_P$1") (pintype "passive"))
      (node (ref "IC11") (pin "7") (pinfunction "V+_7") (pintype "power_in"))
      (node (ref "R87") (pin "P$1") (pinfunction "1_P$1") (pintype "passive"))
    )
    (net (code "33") (name "Net-(C78-2)") (class "Default")
      (node (ref "C76") (pin "2") (pinfunction "2_2") (pintype "passive"))
      (node (ref "C77") (pin "2") (pinfunction "2_2") (pintype "passive"))
      (node (ref "C78") (pin "P$2") (pinfunction "2_P$2") (pintype "passive"))
      (node (ref "IC11") (pin "4") (pinfunction "V-_4") (pintype "power_in"))
      (node (ref "R88") (pin "P$2") (pinfunction "2_P$2") (pintype "passive"))
    )
    (net (code "34") (name "Net-(C79-Pad1)") (class "Default")
      (node (ref "C79") (pin "1") (pinfunction "1_1") (pintype "passive"))
      (node (ref "R90") (pin "2") (pinfunction "2_2") (pintype "passive"))
    )
    (net (code "35") (name "Net-(D11-PadC)") (class "Default")
      (node (ref "D11") (pin "C") (pinfunction "C_C") (pintype "passive"))
      (node (ref "D12") (pin "A") (pinfunction "A_A") (pintype "passive"))
      (node (ref "D6") (pin "A") (pinfunction "A_A") (pintype "passive"))
      (node (ref "D7") (pin "C") (pinfunction "C_C") (pintype "passive"))
    )
    (net (code "36") (name "Net-(D12-PadC)") (class "Default")
      (node (ref "D12") (pin "C") (pinfunction "C_C") (pintype "passive"))
      (node (ref "D13") (pin "A") (pinfunction "A_A") (pintype "passive"))
      (node (ref "D7") (pin "A") (pinfunction "A_A") (pintype "passive"))
      (node (ref "D8") (pin "C") (pinfunction "C_C") (pintype "passive"))
    )
    (net (code "37") (name "Net-(D13-PadC)") (class "Default")
      (node (ref "D13") (pin "C") (pinfunction "C_C") (pintype "passive"))
      (node (ref "D14") (pin "A") (pinfunction "A_A") (pintype "passive"))
      (node (ref "D8") (pin "A") (pinfunction "A_A") (pintype "passive"))
      (node (ref "D9") (pin "C") (pinfunction "C_C") (pintype "passive"))
    )
    (net (code "38") (name "Net-(D15-PadA)") (class "Default")
      (node (ref "D15") (pin "A") (pinfunction "A_A") (pintype "passive"))
      (node (ref "D16") (pin "C") (pinfunction "C_C") (pintype "passive"))
      (node (ref "D20") (pin "C") (pinfunction "C_C") (pintype "passive"))
      (node (ref "D21") (pin "A") (pinfunction "A_A") (pintype "passive"))
    )
    (net (code "39") (name "Net-(D16-PadA)") (class "Default")
      (node (ref "D16") (pin "A") (pinfunction "A_A") (pintype "passive"))
      (node (ref "D17") (pin "C") (pinfunction "C_C") (pintype "passive"))
      (node (ref "D21") (pin "C") (pinfunction "C_C") (pintype "passive"))
      (node (ref "D22") (pin "A") (pinfunction "A_A") (pintype "passive"))
    )
    (net (code "40") (name "Net-(D17-PadA)") (class "Default")
      (node (ref "D17") (pin "A") (pinfunction "A_A") (pintype "passive"))
      (node (ref "D18") (pin "C") (pinfunction "C_C") (pintype "passive"))
      (node (ref "D22") (pin "C") (pinfunction "C_C") (pintype "passive"))
      (node (ref "D23") (pin "A") (pinfunction "A_A") (pintype "passive"))
    )
    (net (code "41") (name "Net-(D18-PadA)") (class "Default")
      (node (ref "D18") (pin "A") (pinfunction "A_A") (pintype "passive"))
      (node (ref "D19") (pin "C") (pinfunction "C_C") (pintype "passive"))
      (node (ref "D23") (pin "C") (pinfunction "C_C") (pintype "passive"))
      (node (ref "D24") (pin "A") (pinfunction "A_A") (pintype "passive"))
    )
    (net (code "42") (name "Net-(H1-MOUNT)") (class "Default")
      (node (ref "H1") (pin "B3,2") (pinfunction "MOUNT_B3,2") (pintype "passive"))
      (node (ref "SJ1") (pin "2") (pinfunction "2_2") (pintype "passive"))
    )
    (net (code "43") (name "Net-(H2-MOUNT)") (class "Default")
      (node (ref "H2") (pin "B3,2") (pinfunction "MOUNT_B3,2") (pintype "passive"))
      (node (ref "SJ2") (pin "2") (pinfunction "2_2") (pintype "passive"))
    )
    (net (code "44") (name "Net-(H3-MOUNT)") (class "Default")
      (node (ref "H3") (pin "B3,2") (pinfunction "MOUNT_B3,2") (pintype "passive"))
      (node (ref "SJ3") (pin "2") (pinfunction "2_2") (pintype "passive"))
    )
    (net (code "45") (name "Net-(H4-MOUNT)") (class "Default")
      (node (ref "H4") (pin "B3,2") (pinfunction "MOUNT_B3,2") (pintype "passive"))
      (node (ref "SJ4") (pin "2") (pinfunction "2_2") (pintype "passive"))
    )
    (net (code "46") (name "Net-(IC1-ADJ)") (class "Default")
      (node (ref "IC1") (pin "4") (pinfunction "ADJ_4") (pintype "input"))
      (node (ref "R4") (pin "P$1") (pinfunction "1_P$1") (pintype "passive"))
      (node (ref "R5") (pin "P$2") (pinfunction "2_P$2") (pintype "passive"))
    )
    (net (code "47") (name "Net-(IC2-ILIM)") (class "Default")
      (node (ref "IC2") (pin "5") (pinfunction "ILIM_5") (pintype "passive"))
      (node (ref "R9") (pin "P$2") (pinfunction "2_P$2") (pintype "passive"))
    )
    (net (code "48") (name "Net-(IC2-PGFB)") (class "Default")
      (node (ref "IC2") (pin "6") (pinfunction "PGFB_6") (pintype "input"))
      (node (ref "R10") (pin "P$1") (pinfunction "1_P$1") (pintype "passive"))
      (node (ref "R11") (pin "P$2") (pinfunction "2_P$2") (pintype "passive"))
    )
    (net (code "49") (name "Net-(IC2-SET)") (class "Default")
      (node (ref "C11") (pin "1") (pinfunction "1_1") (pintype "passive"))
      (node (ref "IC2") (pin "7") (pinfunction "SET_7") (pintype "passive"))
      (node (ref "R7") (pin "P$2") (pinfunction "2_P$2") (pintype "passive"))
    )
    (net (code "50") (name "Net-(IC3-ILIM)") (class "Default")
      (node (ref "IC3") (pin "4") (pinfunction "ILIM_4") (pintype "passive"))
      (node (ref "R3") (pin "P$1") (pinfunction "1_P$1") (pintype "passive"))
    )
    (net (code "51") (name "Net-(IC4-+IN)") (class "Default")
      (node (ref "IC4") (pin "3") (pinfunction "+IN_3") (pintype "input"))
      (node (ref "R29") (pin "P$2") (pinfunction "2_P$2") (pintype "passive"))
    )
    (net (code "52") (name "Net-(IC4-OUT)") (class "Default")
      (node (ref "IC4") (pin "6") (pinfunction "OUT_6") (pintype "output"))
      (node (ref "R30") (pin "1") (pinfunction "1_1") (pintype "passive"))
      (node (ref "R31") (pin "2") (pinfunction "2_2") (pintype "passive"))
      (node (ref "R36") (pin "1") (pinfunction "1_1") (pintype "passive"))
    )
    (net (code "53") (name "Net-(IC7A-IN+)") (class "Default")
      (node (ref "IC7") (pin "3") (pinfunction "IN+_3") (pintype "input"))
      (node (ref "R45") (pin "P$2") (pinfunction "2_P$2") (pintype "passive"))
    )
    (net (code "54") (name "Net-(IC7A-IN-)") (class "Default")
      (node (ref "C57") (pin "2") (pinfunction "2_2") (pintype "passive"))
      (node (ref "IC7") (pin "2") (pinfunction "IN-_2") (pintype "input"))
      (node (ref "R56") (pin "1") (pinfunction "1_1") (pintype "passive"))
    )
    (net (code "55") (name "Net-(IC7A-OUT)") (class "Default")
      (node (ref "C57") (pin "1") (pinfunction "1_1") (pintype "passive"))
      (node (ref "IC7") (pin "1") (pinfunction "OUT_1") (pintype "output"))
      (node (ref "R55") (pin "1") (pinfunction "1_1") (pintype "passive"))
    )
    (net (code "56") (name "Net-(IC7B-IN+)") (class "Default")
      (node (ref "IC7") (pin "5") (pinfunction "IN+_5") (pintype "input"))
      (node (ref "R46") (pin "P$2") (pinfunction "2_P$2") (pintype "passive"))
    )
    (net (code "57") (name "Net-(IC7B-IN-)") (class "Default")
      (node (ref "C58") (pin "2") (pinfunction "2_2") (pintype "passive"))
      (node (ref "IC7") (pin "6") (pinfunction "IN-_6") (pintype "input"))
      (node (ref "R58") (pin "1") (pinfunction "1_1") (pintype "passive"))
    )
    (net (code "58") (name "Net-(IC7B-OUT)") (class "Default")
      (node (ref "C58") (pin "1") (pinfunction "1_1") (pintype "passive"))
      (node (ref "IC7") (pin "7") (pinfunction "OUT_7") (pintype "output"))
      (node (ref "R57") (pin "1") (pinfunction "1_1") (pintype "passive"))
    )
    (net (code "59") (name "Net-(IC8A-IN+)") (class "Default")
      (node (ref "IC8") (pin "3") (pinfunction "IN+_3") (pintype "input"))
      (node (ref "R47") (pin "P$2") (pinfunction "2_P$2") (pintype "passive"))
    )
    (net (code "60") (name "Net-(IC8A-IN-)") (class "Default")
      (node (ref "C59") (pin "2") (pinfunction "2_2") (pintype "passive"))
      (node (ref "IC8") (pin "2") (pinfunction "IN-_2") (pintype "input"))
      (node (ref "R60") (pin "1") (pinfunction "1_1") (pintype "passive"))
    )
    (net (code "61") (name "Net-(IC8A-OUT)") (class "Default")
      (node (ref "C59") (pin "1") (pinfunction "1_1") (pintype "passive"))
      (node (ref "IC8") (pin "1") (pinfunction "OUT_1") (pintype "output"))
      (node (ref "R59") (pin "1") (pinfunction "1_1") (pintype "passive"))
    )
    (net (code "62") (name "Net-(IC8B-IN+)") (class "Default")
      (node (ref "IC8") (pin "5") (pinfunction "IN+_5") (pintype "input"))
      (node (ref "R48") (pin "P$2") (pinfunction "2_P$2") (pintype "passive"))
    )
    (net (code "63") (name "Net-(IC8B-IN-)") (class "Default")
      (node (ref "C60") (pin "2") (pinfunction "2_2") (pintype "passive"))
      (node (ref "IC8") (pin "6") (pinfunction "IN-_6") (pintype "input"))
      (node (ref "R62") (pin "1") (pinfunction "1_1") (pintype "passive"))
    )
    (net (code "64") (name "Net-(IC8B-OUT)") (class "Default")
      (node (ref "C60") (pin "1") (pinfunction "1_1") (pintype "passive"))
      (node (ref "IC8") (pin "7") (pinfunction "OUT_7") (pintype "output"))
      (node (ref "R61") (pin "1") (pinfunction "1_1") (pintype "passive"))
    )
    (net (code "65") (name "Net-(IC9A-IN+)") (class "Default")
      (node (ref "IC9") (pin "3") (pinfunction "IN+_3") (pintype "input"))
      (node (ref "R49") (pin "P$2") (pinfunction "2_P$2") (pintype "passive"))
    )
    (net (code "66") (name "Net-(IC9A-IN-)") (class "Default")
      (node (ref "C61") (pin "2") (pinfunction "2_2") (pintype "passive"))
      (node (ref "IC9") (pin "2") (pinfunction "IN-_2") (pintype "input"))
      (node (ref "R64") (pin "1") (pinfunction "1_1") (pintype "passive"))
    )
    (net (code "67") (name "Net-(IC9A-OUT)") (class "Default")
      (node (ref "C61") (pin "1") (pinfunction "1_1") (pintype "passive"))
      (node (ref "IC9") (pin "1") (pinfunction "OUT_1") (pintype "output"))
      (node (ref "R63") (pin "1") (pinfunction "1_1") (pintype "passive"))
    )
    (net (code "68") (name "Net-(IC9B-IN+)") (class "Default")
      (node (ref "IC9") (pin "5") (pinfunction "IN+_5") (pintype "input"))
      (node (ref "R50") (pin "P$2") (pinfunction "2_P$2") (pintype "passive"))
    )
    (net (code "69") (name "Net-(IC9B-IN-)") (class "Default")
      (node (ref "C62") (pin "2") (pinfunction "2_2") (pintype "passive"))
      (node (ref "IC9") (pin "6") (pinfunction "IN-_6") (pintype "input"))
      (node (ref "R66") (pin "1") (pinfunction "1_1") (pintype "passive"))
    )
    (net (code "70") (name "Net-(IC9B-OUT)") (class "Default")
      (node (ref "C62") (pin "1") (pinfunction "1_1") (pintype "passive"))
      (node (ref "IC9") (pin "7") (pinfunction "OUT_7") (pintype "output"))
      (node (ref "R65") (pin "1") (pinfunction "1_1") (pintype "passive"))
    )
    (net (code "71") (name "Net-(IC10A-IN+)") (class "Default")
      (node (ref "IC10") (pin "3") (pinfunction "IN+_3") (pintype "input"))
      (node (ref "R51") (pin "P$2") (pinfunction "2_P$2") (pintype "passive"))
    )
    (net (code "72") (name "Net-(IC10A-IN-)") (class "Default")
      (node (ref "C63") (pin "2") (pinfunction "2_2") (pintype "passive"))
      (node (ref "IC10") (pin "2") (pinfunction "IN-_2") (pintype "input"))
      (node (ref "R68") (pin "1") (pinfunction "1_1") (pintype "passive"))
    )
    (net (code "73") (name "Net-(IC10A-OUT)") (class "Default")
      (node (ref "C63") (pin "1") (pinfunction "1_1") (pintype "passive"))
      (node (ref "IC10") (pin "1") (pinfunction "OUT_1") (pintype "output"))
      (node (ref "R67") (pin "1") (pinfunction "1_1") (pintype "passive"))
    )
    (net (code "74") (name "Net-(IC10B-IN+)") (class "Default")
      (node (ref "IC10") (pin "5") (pinfunction "IN+_5") (pintype "input"))
      (node (ref "R52") (pin "P$2") (pinfunction "2_P$2") (pintype "passive"))
    )
    (net (code "75") (name "Net-(IC10B-IN-)") (class "Default")
      (node (ref "C64") (pin "2") (pinfunction "2_2") (pintype "passive"))
      (node (ref "IC10") (pin "6") (pinfunction "IN-_6") (pintype "input"))
      (node (ref "R70") (pin "1") (pinfunction "1_1") (pintype "passive"))
    )
    (net (code "76") (name "Net-(IC10B-OUT)") (class "Default")
      (node (ref "C64") (pin "1") (pinfunction "1_1") (pintype "passive"))
      (node (ref "IC10") (pin "7") (pinfunction "OUT_7") (pintype "output"))
      (node (ref "R69") (pin "1") (pinfunction "1_1") (pintype "passive"))
    )
    (net (code "77") (name "Net-(IC11-+IN)") (class "Default")
      (node (ref "IC11") (pin "3") (pinfunction "+IN_3") (pintype "input"))
      (node (ref "R85") (pin "P$2") (pinfunction "2_P$2") (pintype "passive"))
    )
    (net (code "78") (name "Net-(IC11--IN)") (class "Default")
      (node (ref "IC11") (pin "2") (pinfunction "-IN_2") (pintype "input"))
      (node (ref "IC11") (pin "6") (pinfunction "OUT_6") (pintype "output"))
      (node (ref "R89") (pin "P$2") (pinfunction "2_P$2") (pintype "passive"))
    )
    (net (code "79") (name "Net-(IC12-+IN)") (class "Default")
      (node (ref "IC12") (pin "3") (pinfunction "+IN_3") (pintype "input"))
      (node (ref "R93") (pin "P$2") (pinfunction "2_P$2") (pintype "passive"))
    )
    (net (code "80") (name "Net-(IC12--IN)") (class "Default")
      (node (ref "IC12") (pin "2") (pinfunction "-IN_2") (pintype "input"))
      (node (ref "R92") (pin "P$2") (pinfunction "2_P$2") (pintype "passive"))
      (node (ref "R94") (pin "P$1") (pinfunction "1_P$1") (pintype "passive"))
    )
    (net (code "81") (name "Net-(IC12-OUT)") (class "Default")
      (node (ref "IC12") (pin "6") (pinfunction "OUT_6") (pintype "output"))
      (node (ref "K8") (pin "1") (pinfunction "1_1") (pintype "passive"))
      (node (ref "R94") (pin "P$2") (pinfunction "2_P$2") (pintype "passive"))
    )
    (net (code "82") (name "Net-(LD2-C)") (class "Default")
      (node (ref "LD2") (pin "K") (pinfunction "C_K") (pintype "passive"))
      (node (ref "R22") (pin "P$2") (pinfunction "2_P$2") (pintype "passive"))
    )
    (net (code "83") (name "Net-(R1-A)") (class "Default")
      (node (ref "R1") (pin "1") (pinfunction "A_1") (pintype "passive"))
      (node (ref "R2") (pin "P$2") (pinfunction "2_P$2") (pintype "passive"))
    )
    (net (code "84") (name "Net-(R5-1)") (class "Default")
      (node (ref "R5") (pin "P$1") (pinfunction "1_P$1") (pintype "passive"))
      (node (ref "R6") (pin "3") (pinfunction "E_3") (pintype "passive"))
    )
    (net (code "85") (name "Net-(R7-1)") (class "Default")
      (node (ref "R7") (pin "P$1") (pinfunction "1_P$1") (pintype "passive"))
      (node (ref "R8") (pin "1") (pinfunction "A_1") (pintype "passive"))
    )
    (net (code "86") (name "Net-(R12-S)") (class "Default")
      (node (ref "R12") (pin "2") (pinfunction "S_2") (pintype "passive"))
      (node (ref "R13") (pin "P$1") (pinfunction "1_P$1") (pintype "passive"))
    )
    (net (code "87") (name "Net-(R13-2)") (class "Default")
      (node (ref "C20") (pin "1") (pinfunction "1_1") (pintype "passive"))
      (node (ref "R13") (pin "P$2") (pinfunction "2_P$2") (pintype "passive"))
      (node (ref "R14") (pin "P$1") (pinfunction "1_P$1") (pintype "passive"))
      (node (ref "R15") (pin "P$2") (pinfunction "2_P$2") (pintype "passive"))
    )
    (net (code "88") (name "Net-(R14-2)") (class "Default")
      (node (ref "R14") (pin "P$2") (pinfunction "2_P$2") (pintype "passive"))
      (node (ref "R19") (pin "P$2") (pinfunction "2_P$2") (pintype "passive"))
      (node (ref "R29") (pin "P$1") (pinfunction "1_P$1") (pintype "passive"))
    )
    (net (code "89") (name "Net-(R16-1)") (class "Default")
      (node (ref "D10") (pin "C") (pinfunction "C_C") (pintype "passive"))
      (node (ref "D11") (pin "A") (pinfunction "A_A") (pintype "passive"))
      (node (ref "D5") (pin "A") (pinfunction "A_A") (pintype "passive"))
      (node (ref "D6") (pin "C") (pinfunction "C_C") (pintype "passive"))
      (node (ref "R16") (pin "P$1") (pinfunction "1_P$1") (pintype "passive"))
      (node (ref "R17") (pin "1") (pinfunction "1_1") (pintype "passive"))
      (node (ref "R18") (pin "P$2") (pinfunction "2_P$2") (pintype "passive"))
    )
    (net (code "90") (name "Net-(R19-1)") (class "Default")
      (node (ref "D10") (pin "A") (pinfunction "A_A") (pintype "passive"))
      (node (ref "D5") (pin "C") (pinfunction "C_C") (pintype "passive"))
      (node (ref "K2") (pin "1") (pinfunction "1_1") (pintype "passive"))
      (node (ref "R19") (pin "P$1") (pinfunction "1_P$1") (pintype "passive"))
      (node (ref "R85") (pin "P$1") (pinfunction "1_P$1") (pintype "passive"))
      (node (ref "R93") (pin "P$1") (pinfunction "1_P$1") (pintype "passive"))
      (node (ref "X2") (pin "1") (pinfunction "1_1") (pintype "passive"))
    )
    (net (code "91") (name "Net-(R20-E)") (class "Default")
      (node (ref "R20") (pin "3") (pinfunction "E_3") (pintype "passive"))
      (node (ref "R25") (pin "2") (pinfunction "2_2") (pintype "passive"))
    )
    (net (code "92") (name "Net-(R21-1)") (class "Default")
      (node (ref "LD1") (pin "A") (pinfunction "A_A") (pintype "passive"))
      (node (ref "R21") (pin "P$1") (pinfunction "1_P$1") (pintype "passive"))
    )
    (net (code "93") (name "Net-(R41-2)") (class "Default")
      (node (ref "IC5") (pin "2") (pinfunction "OUT_2") (pintype "output"))
      (node (ref "IC5") (pin "3") (pinfunction "OUT_3") (pintype "output"))
      (node (ref "IC5") (pin "4") (pinfunction "OUT_4") (pintype "output"))
      (node (ref "R41") (pin "P$2") (pinfunction "2_P$2") (pintype "passive"))
    )
    (net (code "94") (name "Net-(R42-1)") (class "Default")
      (node (ref "C51") (pin "+") (pinfunction "+_+") (pintype "passive"))
      (node (ref "C53") (pin "1") (pinfunction "1_1") (pintype "passive"))
      (node (ref "D25") (pin "C") (pinfunction "C_C") (pintype "passive"))
      (node (ref "R42") (pin "P$1") (pinfunction "1_P$1") (pintype "passive"))
      (node (ref "R45") (pin "P$1") (pinfunction "1_P$1") (pintype "passive"))
      (node (ref "R46") (pin "P$1") (pinfunction "1_P$1") (pintype "passive"))
      (node (ref "R47") (pin "P$1") (pinfunction "1_P$1") (pintype "passive"))
      (node (ref "R48") (pin "P$1") (pinfunction "1_P$1") (pintype "passive"))
    )
    (net (code "95") (name "Net-(R43-1)") (class "Default")
      (node (ref "C56") (pin "1") (pinfunction "1_1") (pintype "passive"))
      (node (ref "IC6") (pin "7") (pinfunction "IN_7") (pintype "power_in"))
      (node (ref "IC6") (pin "8") (pinfunction "IN_8") (pintype "power_in"))
      (node (ref "R43") (pin "P$1") (pinfunction "1_P$1") (pintype "passive"))
    )
    (net (code "96") (name "Net-(R43-2)") (class "Default")
      (node (ref "C52") (pin "-") (pinfunction "-_-") (pintype "passive"))
      (node (ref "C54") (pin "2") (pinfunction "2_2") (pintype "passive"))
      (node (ref "D26") (pin "A") (pinfunction "A_A") (pintype "passive"))
      (node (ref "R43") (pin "P$2") (pinfunction "2_P$2") (pintype "passive"))
      (node (ref "R49") (pin "P$1") (pinfunction "1_P$1") (pintype "passive"))
      (node (ref "R50") (pin "P$1") (pinfunction "1_P$1") (pintype "passive"))
      (node (ref "R51") (pin "P$1") (pinfunction "1_P$1") (pintype "passive"))
      (node (ref "R52") (pin "P$1") (pinfunction "1_P$1") (pintype "passive"))
    )
    (net (code "97") (name "Net-(R44-2)") (class "Default")
      (node (ref "IC6") (pin "2") (pinfunction "OUT_2") (pintype "output"))
      (node (ref "IC6") (pin "3") (pinfunction "OUT_3") (pintype "output"))
      (node (ref "IC6") (pin "4") (pinfunction "OUT_4") (pintype "output"))
      (node (ref "R44") (pin "P$2") (pinfunction "2_P$2") (pintype "passive"))
    )
    (net (code "98") (name "Net-(R55-Pad2)") (class "Default")
      (node (ref "R55") (pin "2") (pinfunction "2_2") (pintype "passive"))
      (node (ref "R56") (pin "2") (pinfunction "2_2") (pintype "passive"))
      (node (ref "R71") (pin "1") (pinfunction "1_1") (pintype "passive"))
    )
    (net (code "99") (name "Net-(R57-Pad2)") (class "Default")
      (node (ref "R57") (pin "2") (pinfunction "2_2") (pintype "passive"))
      (node (ref "R58") (pin "2") (pinfunction "2_2") (pintype "passive"))
      (node (ref "R72") (pin "1") (pinfunction "1_1") (pintype "passive"))
    )
    (net (code "100") (name "Net-(R59-Pad2)") (class "Default")
      (node (ref "R59") (pin "2") (pinfunction "2_2") (pintype "passive"))
      (node (ref "R60") (pin "2") (pinfunction "2_2") (pintype "passive"))
      (node (ref "R73") (pin "1") (pinfunction "1_1") (pintype "passive"))
    )
    (net (code "101") (name "Net-(R61-Pad2)") (class "Default")
      (node (ref "R61") (pin "2") (pinfunction "2_2") (pintype "passive"))
      (node (ref "R62") (pin "2") (pinfunction "2_2") (pintype "passive"))
      (node (ref "R74") (pin "1") (pinfunction "1_1") (pintype "passive"))
    )
    (net (code "102") (name "Net-(R63-Pad2)") (class "Default")
      (node (ref "R63") (pin "2") (pinfunction "2_2") (pintype "passive"))
      (node (ref "R64") (pin "2") (pinfunction "2_2") (pintype "passive"))
      (node (ref "R75") (pin "1") (pinfunction "1_1") (pintype "passive"))
    )
    (net (code "103") (name "Net-(R65-Pad2)") (class "Default")
      (node (ref "R65") (pin "2") (pinfunction "2_2") (pintype "passive"))
      (node (ref "R66") (pin "2") (pinfunction "2_2") (pintype "passive"))
      (node (ref "R76") (pin "1") (pinfunction "1_1") (pintype "passive"))
    )
    (net (code "104") (name "Net-(R67-Pad2)") (class "Default")
      (node (ref "R67") (pin "2") (pinfunction "2_2") (pintype "passive"))
      (node (ref "R68") (pin "2") (pinfunction "2_2") (pintype "passive"))
      (node (ref "R77") (pin "1") (pinfunction "1_1") (pintype "passive"))
    )
    (net (code "105") (name "Net-(R69-Pad2)") (class "Default")
      (node (ref "R69") (pin "2") (pinfunction "2_2") (pintype "passive"))
      (node (ref "R70") (pin "2") (pinfunction "2_2") (pintype "passive"))
      (node (ref "R78") (pin "1") (pinfunction "1_1") (pintype "passive"))
    )
    (net (code "106") (name "Net-(R84-Pad2)") (class "Default")
      (node (ref "R84") (pin "2") (pinfunction "2_2") (pintype "passive"))
      (node (ref "X3") (pin "1") (pinfunction "1_1") (pintype "passive"))
    )
    (net (code "107") (name "Net-(R91-S)") (class "Default")
      (node (ref "R91") (pin "2") (pinfunction "S_2") (pintype "passive"))
      (node (ref "R92") (pin "P$1") (pinfunction "1_P$1") (pintype "passive"))
    )
    (net (code "108") (name "unconnected-(IC2-PG-Pad4)") (class "Default")
      (node (ref "IC2") (pin "4") (pinfunction "PG_4") (pintype "passive"))
    )
    (net (code "109") (name "unconnected-(IC5-NC-Pad1)") (class "Default")
      (node (ref "IC5") (pin "1") (pinfunction "NC_1") (pintype "no_connect"))
    )
    (net (code "110") (name "unconnected-(IC5-NC-Pad6)") (class "Default")
      (node (ref "IC5") (pin "6") (pinfunction "NC_6") (pintype "no_connect"))
    )
    (net (code "111") (name "unconnected-(IC6-NC-Pad1)") (class "Default")
      (node (ref "IC6") (pin "1") (pinfunction "NC_1") (pintype "no_connect"))
    )
    (net (code "112") (name "unconnected-(IC6-NC-Pad6)") (class "Default")
      (node (ref "IC6") (pin "6") (pinfunction "NC_6") (pintype "no_connect"))
    )
  )
)
